# NucciF.net
KiCad netlist of a schematic drawn in Altium Designer
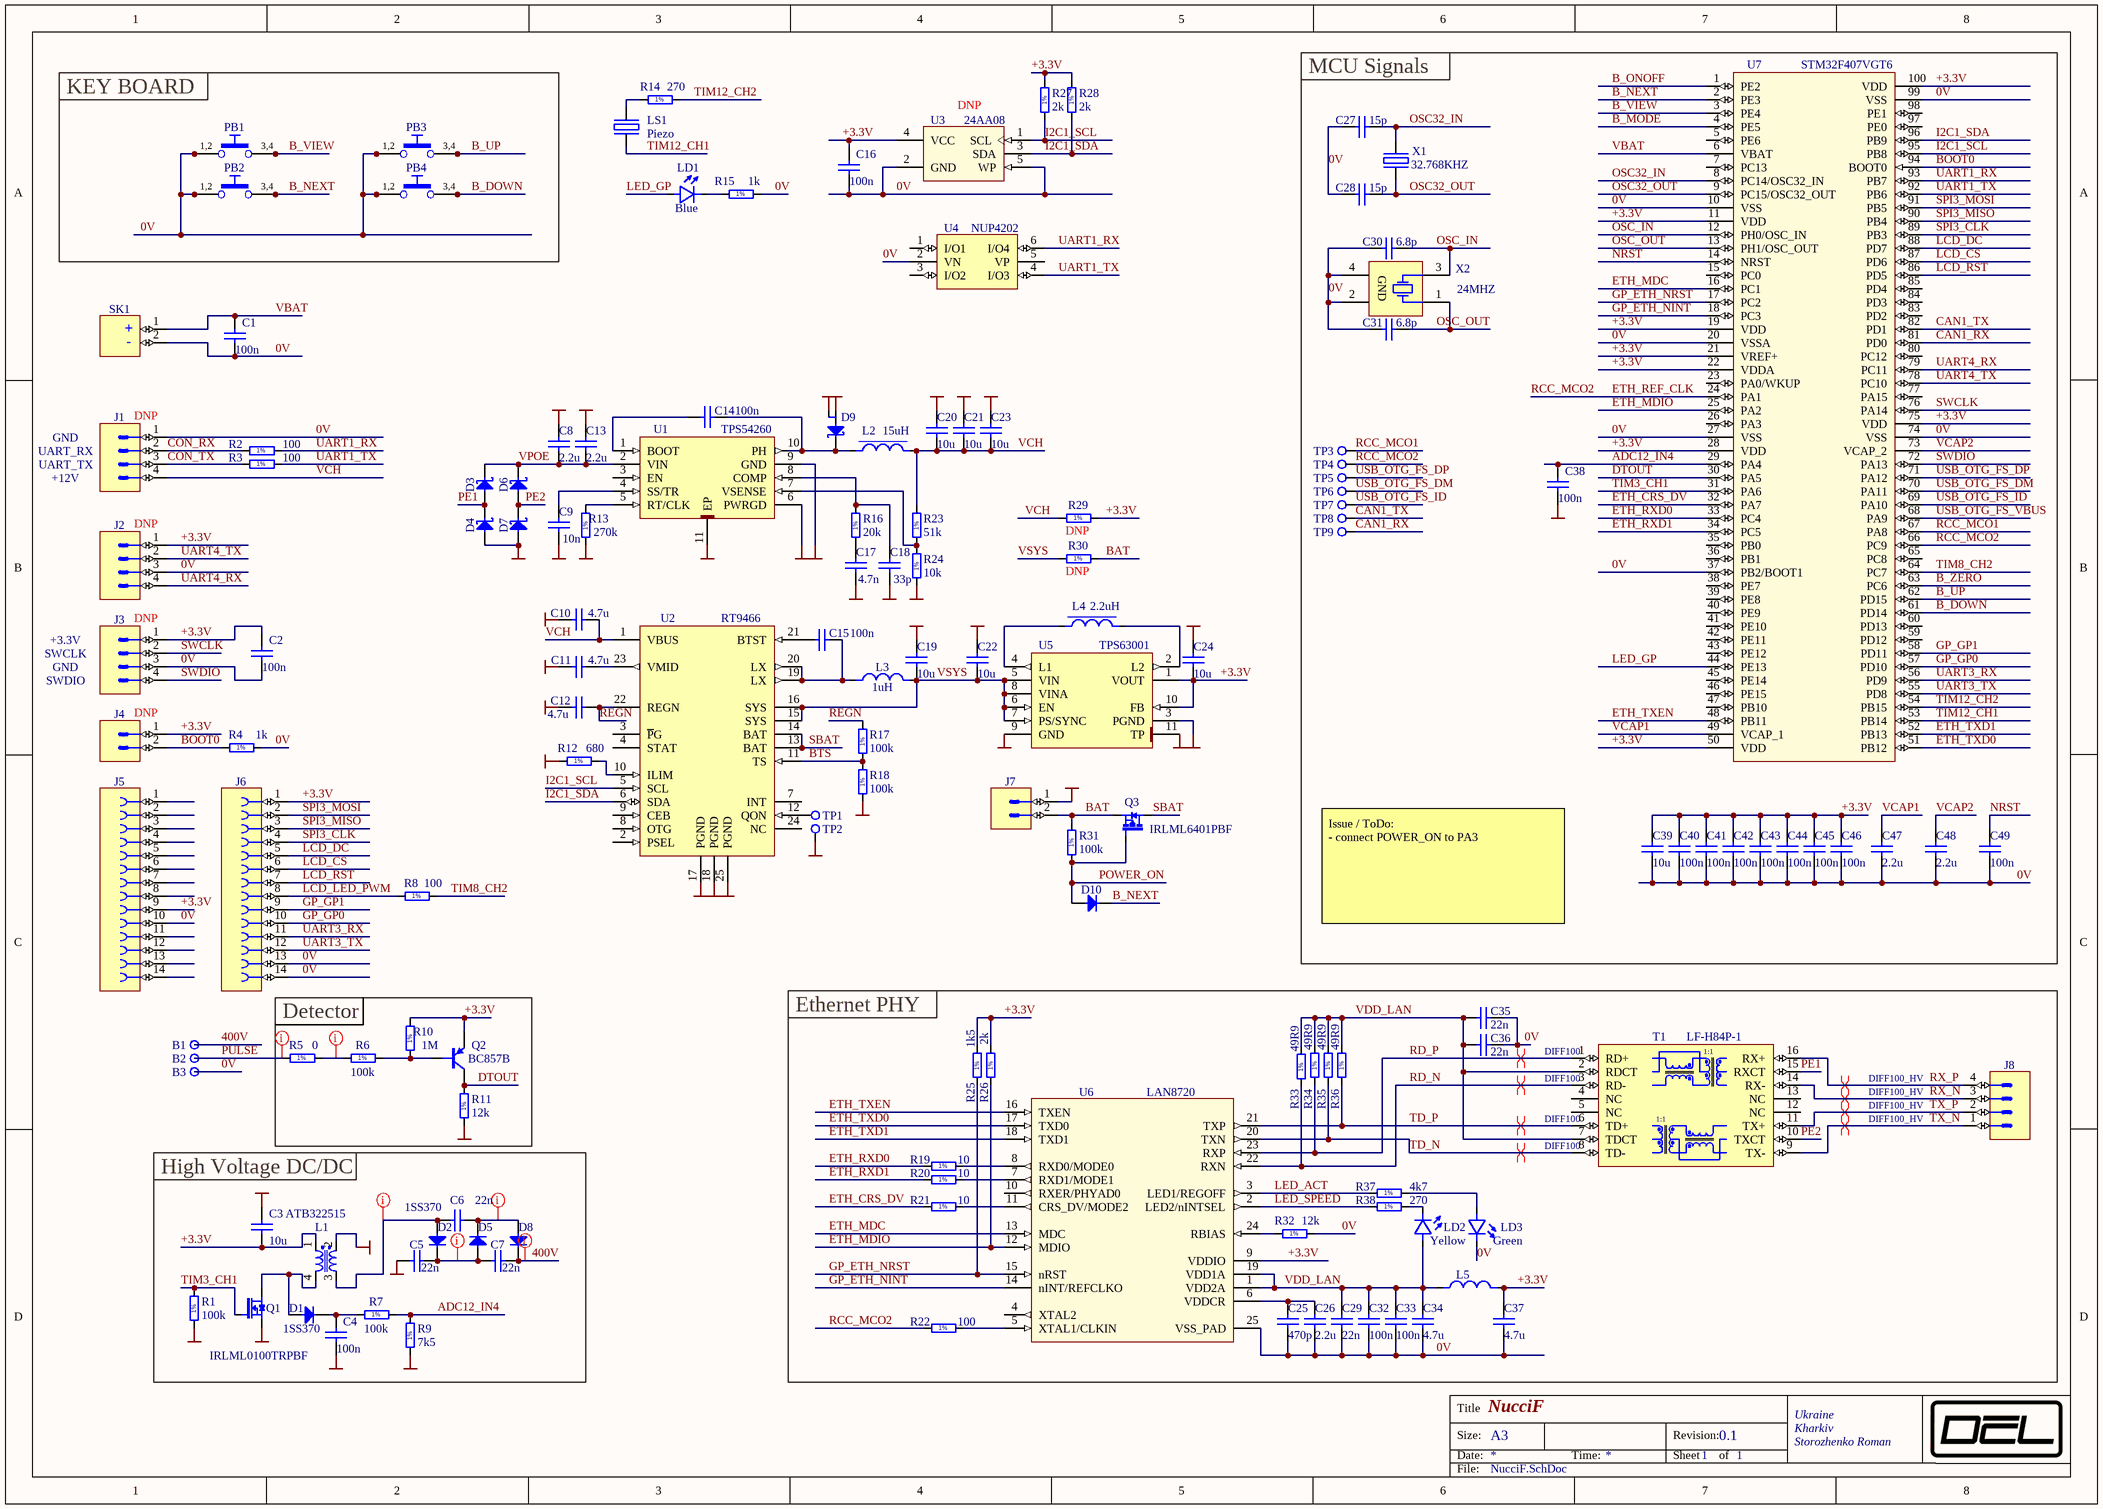
[diagram p0: NucciF.SchDoc]

(export (version "E")
  (design (tool "Eeschema 10.0.6"))
  (components
    (comp (ref "B1")
      (value "V")
      (footprint "c150h100")
      (description "Single Terminal Socket")
      (fields (field (name "PART NUMBER") "PLATED_HOLE1.0_PAD1.5") (field (name "AUTHOR") "CERN DEM JLC"))
      (libsource (lib "Eletro-mechanical") (part "Single Terminal Socket"))
    )
    (comp (ref "B2")
      (value "P")
      (footprint "c150h100")
      (description "Single Terminal Socket")
      (fields (field (name "PART NUMBER") "PLATED_HOLE1.0_PAD1.5") (field (name "AUTHOR") "CERN DEM JLC"))
      (libsource (lib "Eletro-mechanical") (part "Single Terminal Socket"))
    )
    (comp (ref "B3")
      (value "G")
      (footprint "c150h100")
      (description "Single Terminal Socket")
      (fields (field (name "PART NUMBER") "PLATED_HOLE1.0_PAD1.5") (field (name "AUTHOR") "CERN DEM JLC"))
      (libsource (lib "Eletro-mechanical") (part "Single Terminal Socket"))
    )
    (comp (ref "C1")
      (value "100n")
      (footprint "CAPC1005X55N")
      (description "Non-polarised capacitor")
      (fields
        (field (name "PART NUMBER") "CC0402_100NF_50V_10%_X7R")
        (field (name "VOLTAGE") "50V")
        (field (name "AUTHOR") "DEL")
      )
      (libsource (lib "Capacitors") (part "Capacitor - non polarized"))
    )
    (comp (ref "C2")
      (value "100n")
      (footprint "CAPC1005X55N")
      (description "Non-polarised capacitor")
      (fields
        (field (name "PART NUMBER") "CC0402_100NF_50V_10%_X7R")
        (field (name "VOLTAGE") "50V")
        (field (name "AUTHOR") "DEL")
      )
      (libsource (lib "Capacitors") (part "Capacitor - non polarized"))
    )
    (comp (ref "C3")
      (value "10u")
      (footprint "CAPC1608X87N")
      (description "Non-polarised capacitor")
      (fields
        (field (name "PART NUMBER") "CC0603_10UF_10V_20%_X5R")
        (field (name "VOLTAGE") "10V")
        (field (name "AUTHOR") "CERN DEM JLC")
      )
      (libsource (lib "Capacitors") (part "Capacitor - non polarized"))
    )
    (comp (ref "C4")
      (value "100n")
      (footprint "CAPC1005X55N")
      (description "Non-polarised capacitor")
      (fields
        (field (name "PART NUMBER") "CC0402_100NF_50V_10%_X7R")
        (field (name "VOLTAGE") "50V")
        (field (name "AUTHOR") "DEL")
      )
      (libsource (lib "Capacitors") (part "Capacitor - non polarized"))
    )
    (comp (ref "C5")
      (value "22n")
      (footprint "CAPC2012X135N")
      (description "Non-polarised capacitor")
      (fields
        (field (name "PART NUMBER") "CC0805_22NF_500V_10%_X7R")
        (field (name "VOLTAGE") "500V")
        (field (name "AUTHOR") "DEL")
      )
      (libsource (lib "Capacitors") (part "Capacitor - non polarized"))
    )
    (comp (ref "C6")
      (value "22n")
      (footprint "CAPC2012X135N")
      (description "Non-polarised capacitor")
      (fields
        (field (name "PART NUMBER") "CC0805_22NF_500V_10%_X7R")
        (field (name "VOLTAGE") "500V")
        (field (name "AUTHOR") "DEL")
      )
      (libsource (lib "Capacitors") (part "Capacitor - non polarized"))
    )
    (comp (ref "C7")
      (value "22n")
      (footprint "CAPC2012X135N")
      (description "Non-polarised capacitor")
      (fields
        (field (name "PART NUMBER") "CC0805_22NF_500V_10%_X7R")
        (field (name "VOLTAGE") "500V")
        (field (name "AUTHOR") "DEL")
      )
      (libsource (lib "Capacitors") (part "Capacitor - non polarized"))
    )
    (comp (ref "C8")
      (value "2.2u")
      (footprint "CAPC3216X140N")
      (description "Non-polarised capacitor")
      (fields
        (field (name "PART NUMBER") "CC1206_2.2UF_100V_10%_X7R")
        (field (name "VOLTAGE") "100V")
        (field (name "AUTHOR") "DEL")
      )
      (libsource (lib "Capacitors") (part "Capacitor - non polarized"))
    )
    (comp (ref "C9")
      (value "10n")
      (footprint "CAPC1005X55N")
      (description "Non-polarised capacitor")
      (fields
        (field (name "PART NUMBER") "CC0402_10NF_16V_10%_X7R")
        (field (name "VOLTAGE") "16V")
        (field (name "AUTHOR") "CERN DEM JLC")
      )
      (libsource (lib "Capacitors") (part "Capacitor - non polarized"))
    )
    (comp (ref "C10")
      (value "4.7u")
      (footprint "CAPC1005X55N")
      (description "Non-polarised capacitor")
      (fields
        (field (name "PART NUMBER") "CC0402_4.7UF_10V_20%_X5R")
        (field (name "VOLTAGE") "10V")
        (field (name "AUTHOR") "DEL")
      )
      (libsource (lib "Capacitors") (part "Capacitor - non polarized"))
    )
    (comp (ref "C11")
      (value "4.7u")
      (footprint "CAPC1005X55N")
      (description "Non-polarised capacitor")
      (fields
        (field (name "PART NUMBER") "CC0402_4.7UF_10V_20%_X5R")
        (field (name "VOLTAGE") "10V")
        (field (name "AUTHOR") "DEL")
      )
      (libsource (lib "Capacitors") (part "Capacitor - non polarized"))
    )
    (comp (ref "C12")
      (value "4.7u")
      (footprint "CAPC1005X55N")
      (description "Non-polarised capacitor")
      (fields
        (field (name "PART NUMBER") "CC0402_4.7UF_10V_20%_X5R")
        (field (name "VOLTAGE") "10V")
        (field (name "AUTHOR") "DEL")
      )
      (libsource (lib "Capacitors") (part "Capacitor - non polarized"))
    )
    (comp (ref "C13")
      (value "2.2u")
      (footprint "CAPC3216X140N")
      (description "Non-polarised capacitor")
      (fields
        (field (name "PART NUMBER") "CC1206_2.2UF_100V_10%_X7R")
        (field (name "VOLTAGE") "100V")
        (field (name "AUTHOR") "DEL")
      )
      (libsource (lib "Capacitors") (part "Capacitor - non polarized"))
    )
    (comp (ref "C14")
      (value "100n")
      (footprint "CAPC1005X55N")
      (description "Non-polarised capacitor")
      (fields
        (field (name "PART NUMBER") "CC0402_100NF_16V_10%_X7R")
        (field (name "VOLTAGE") "16V")
        (field (name "AUTHOR") "CERN DEM JLC")
      )
      (libsource (lib "Capacitors") (part "Capacitor - non polarized"))
    )
    (comp (ref "C15")
      (value "100n")
      (footprint "CAPC1005X55N")
      (description "Non-polarised capacitor")
      (fields
        (field (name "PART NUMBER") "CC0402_100NF_16V_10%_X7R")
        (field (name "VOLTAGE") "16V")
        (field (name "AUTHOR") "CERN DEM JLC")
      )
      (libsource (lib "Capacitors") (part "Capacitor - non polarized"))
    )
    (comp (ref "C16")
      (value "100n")
      (footprint "CAPC1005X55N")
      (description "Non-polarised capacitor")
      (fields
        (field (name "PART NUMBER") "CC0402_100NF_50V_10%_X7R")
        (field (name "VOLTAGE") "50V")
        (field (name "AUTHOR") "DEL")
      )
      (libsource (lib "Capacitors") (part "Capacitor - non polarized"))
    )
    (comp (ref "C17")
      (value "4.7n")
      (footprint "CAPC1005X55N")
      (description "Non-polarised capacitor")
      (fields
        (field (name "PART NUMBER") "CC0402_4.7NF_16V_10%_X7R")
        (field (name "VOLTAGE") "16V")
        (field (name "AUTHOR") "CERN DEM JLC")
      )
      (libsource (lib "Capacitors") (part "Capacitor - non polarized"))
    )
    (comp (ref "C18")
      (value "33p")
      (footprint "CAPC1005X55N")
      (description "Non-polarised capacitor")
      (fields
        (field (name "PART NUMBER") "CC0402_33PF_50V_5%_NP0")
        (field (name "VOLTAGE") "50V")
        (field (name "AUTHOR") "CERN DEM JLC")
      )
      (libsource (lib "Capacitors") (part "Capacitor - non polarized"))
    )
    (comp (ref "C19")
      (value "10u")
      (footprint "CAPC1608X87N")
      (description "Non-polarised capacitor")
      (fields
        (field (name "PART NUMBER") "CC0603_10UF_10V_20%_X5R")
        (field (name "VOLTAGE") "10V")
        (field (name "AUTHOR") "CERN DEM JLC")
      )
      (libsource (lib "Capacitors") (part "Capacitor - non polarized"))
    )
    (comp (ref "C20")
      (value "10u")
      (footprint "CAPC1608X87N")
      (description "Non-polarised capacitor")
      (fields
        (field (name "PART NUMBER") "CC0603_10UF_10V_20%_X5R")
        (field (name "VOLTAGE") "10V")
        (field (name "AUTHOR") "CERN DEM JLC")
      )
      (libsource (lib "Capacitors") (part "Capacitor - non polarized"))
    )
    (comp (ref "C21")
      (value "10u")
      (footprint "CAPC1608X87N")
      (description "Non-polarised capacitor")
      (fields
        (field (name "PART NUMBER") "CC0603_10UF_10V_20%_X5R")
        (field (name "VOLTAGE") "10V")
        (field (name "AUTHOR") "CERN DEM JLC")
      )
      (libsource (lib "Capacitors") (part "Capacitor - non polarized"))
    )
    (comp (ref "C22")
      (value "10u")
      (footprint "CAPC1608X87N")
      (description "Non-polarised capacitor")
      (fields
        (field (name "PART NUMBER") "CC0603_10UF_10V_20%_X5R")
        (field (name "VOLTAGE") "10V")
        (field (name "AUTHOR") "CERN DEM JLC")
      )
      (libsource (lib "Capacitors") (part "Capacitor - non polarized"))
    )
    (comp (ref "C23")
      (value "10u")
      (footprint "CAPC1608X87N")
      (description "Non-polarised capacitor")
      (fields
        (field (name "PART NUMBER") "CC0603_10UF_10V_20%_X5R")
        (field (name "VOLTAGE") "10V")
        (field (name "AUTHOR") "CERN DEM JLC")
      )
      (libsource (lib "Capacitors") (part "Capacitor - non polarized"))
    )
    (comp (ref "C24")
      (value "10u")
      (footprint "CAPC1608X87N")
      (description "Non-polarised capacitor")
      (fields
        (field (name "PART NUMBER") "CC0603_10UF_10V_20%_X5R")
        (field (name "VOLTAGE") "10V")
        (field (name "AUTHOR") "CERN DEM JLC")
      )
      (libsource (lib "Capacitors") (part "Capacitor - non polarized"))
    )
    (comp (ref "C25")
      (value "470p")
      (footprint "CAPC1005X55N")
      (description "Non-polarised capacitor")
      (fields
        (field (name "PART NUMBER") "CC0402_470PF_50V_10%_X7R")
        (field (name "VOLTAGE") "50V")
        (field (name "AUTHOR") "CERN DEM JLC")
      )
      (libsource (lib "Capacitors") (part "Capacitor - non polarized"))
    )
    (comp (ref "C26")
      (value "2.2u")
      (footprint "CAPC1005X55N")
      (description "Non-polarised capacitor")
      (fields
        (field (name "PART NUMBER") "CC0402_2.2UF_6.3V_20%_X5R")
        (field (name "VOLTAGE") "6.3V")
        (field (name "AUTHOR") "ELMAN")
      )
      (libsource (lib "Capacitors") (part "Capacitor - non polarized"))
    )
    (comp (ref "C27")
      (value "15p")
      (footprint "CAPC1005X55N")
      (description "Non-polarised capacitor")
      (fields
        (field (name "PART NUMBER") "CC0402_15PF_50V_5%_NP0")
        (field (name "VOLTAGE") "50V")
        (field (name "AUTHOR") "CERN DEM JLC")
      )
      (libsource (lib "Capacitors") (part "Capacitor - non polarized"))
    )
    (comp (ref "C28")
      (value "15p")
      (footprint "CAPC1005X55N")
      (description "Non-polarised capacitor")
      (fields
        (field (name "PART NUMBER") "CC0402_15PF_50V_5%_NP0")
        (field (name "VOLTAGE") "50V")
        (field (name "AUTHOR") "CERN DEM JLC")
      )
      (libsource (lib "Capacitors") (part "Capacitor - non polarized"))
    )
    (comp (ref "C29")
      (value "22n")
      (footprint "CAPC1005X55N")
      (description "Non-polarised capacitor")
      (fields
        (field (name "PART NUMBER") "CC0402_22NF_16V_10%_X7R")
        (field (name "VOLTAGE") "16V")
        (field (name "AUTHOR") "CERN DEM JLC")
      )
      (libsource (lib "Capacitors") (part "Capacitor - non polarized"))
    )
    (comp (ref "C30")
      (value "6.8p")
      (footprint "CAPC1005X55N")
      (description "Non-polarised capacitor")
      (fields
        (field (name "PART NUMBER") "CC0402_6.8PF_50V_0.5PF_NP0")
        (field (name "VOLTAGE") "50V")
        (field (name "AUTHOR") "CERN DEM JLC")
      )
      (libsource (lib "Capacitors") (part "Capacitor - non polarized"))
    )
    (comp (ref "C31")
      (value "6.8p")
      (footprint "CAPC1005X55N")
      (description "Non-polarised capacitor")
      (fields
        (field (name "PART NUMBER") "CC0402_6.8PF_50V_0.5PF_NP0")
        (field (name "VOLTAGE") "50V")
        (field (name "AUTHOR") "CERN DEM JLC")
      )
      (libsource (lib "Capacitors") (part "Capacitor - non polarized"))
    )
    (comp (ref "C32")
      (value "100n")
      (footprint "CAPC1005X55N")
      (description "Non-polarised capacitor")
      (fields
        (field (name "PART NUMBER") "CC0402_100NF_50V_10%_X7R")
        (field (name "VOLTAGE") "50V")
        (field (name "AUTHOR") "DEL")
      )
      (libsource (lib "Capacitors") (part "Capacitor - non polarized"))
    )
    (comp (ref "C33")
      (value "100n")
      (footprint "CAPC1005X55N")
      (description "Non-polarised capacitor")
      (fields
        (field (name "PART NUMBER") "CC0402_100NF_50V_10%_X7R")
        (field (name "VOLTAGE") "50V")
        (field (name "AUTHOR") "DEL")
      )
      (libsource (lib "Capacitors") (part "Capacitor - non polarized"))
    )
    (comp (ref "C34")
      (value "4.7u")
      (footprint "CAPC1608X87N")
      (description "Non-polarised capacitor")
      (fields
        (field (name "PART NUMBER") "CC0603_4.7UF_10V_10%_X5R")
        (field (name "VOLTAGE") "10V")
        (field (name "AUTHOR") "ELMAN")
      )
      (libsource (lib "Capacitors") (part "Capacitor - non polarized"))
    )
    (comp (ref "C35")
      (value "22n")
      (footprint "CAPC1005X55N")
      (description "Non-polarised capacitor")
      (fields
        (field (name "PART NUMBER") "CC0402_22NF_16V_10%_X7R")
        (field (name "VOLTAGE") "16V")
        (field (name "AUTHOR") "CERN DEM JLC")
      )
      (libsource (lib "Capacitors") (part "Capacitor - non polarized"))
    )
    (comp (ref "C36")
      (value "22n")
      (footprint "CAPC1005X55N")
      (description "Non-polarised capacitor")
      (fields
        (field (name "PART NUMBER") "CC0402_22NF_16V_10%_X7R")
        (field (name "VOLTAGE") "16V")
        (field (name "AUTHOR") "CERN DEM JLC")
      )
      (libsource (lib "Capacitors") (part "Capacitor - non polarized"))
    )
    (comp (ref "C37")
      (value "4.7u")
      (footprint "CAPC1608X87N")
      (description "Non-polarised capacitor")
      (fields
        (field (name "PART NUMBER") "CC0603_4.7UF_10V_10%_X5R")
        (field (name "VOLTAGE") "10V")
        (field (name "AUTHOR") "ELMAN")
      )
      (libsource (lib "Capacitors") (part "Capacitor - non polarized"))
    )
    (comp (ref "C38")
      (value "100n")
      (footprint "CAPC1005X55N")
      (description "Non-polarised capacitor")
      (fields
        (field (name "PART NUMBER") "CC0402_100NF_50V_10%_X7R")
        (field (name "VOLTAGE") "50V")
        (field (name "AUTHOR") "DEL")
      )
      (libsource (lib "Capacitors") (part "Capacitor - non polarized"))
    )
    (comp (ref "C39")
      (value "10u")
      (footprint "CAPC1608X87N")
      (description "Non-polarised capacitor")
      (fields
        (field (name "PART NUMBER") "CC0603_10UF_10V_20%_X5R")
        (field (name "VOLTAGE") "10V")
        (field (name "AUTHOR") "CERN DEM JLC")
      )
      (libsource (lib "Capacitors") (part "Capacitor - non polarized"))
    )
    (comp (ref "C40")
      (value "100n")
      (footprint "CAPC1005X55N")
      (description "Non-polarised capacitor")
      (fields
        (field (name "PART NUMBER") "CC0402_100NF_50V_10%_X7R")
        (field (name "VOLTAGE") "50V")
        (field (name "AUTHOR") "DEL")
      )
      (libsource (lib "Capacitors") (part "Capacitor - non polarized"))
    )
    (comp (ref "C41")
      (value "100n")
      (footprint "CAPC1005X55N")
      (description "Non-polarised capacitor")
      (fields
        (field (name "PART NUMBER") "CC0402_100NF_50V_10%_X7R")
        (field (name "VOLTAGE") "50V")
        (field (name "AUTHOR") "DEL")
      )
      (libsource (lib "Capacitors") (part "Capacitor - non polarized"))
    )
    (comp (ref "C42")
      (value "100n")
      (footprint "CAPC1005X55N")
      (description "Non-polarised capacitor")
      (fields
        (field (name "PART NUMBER") "CC0402_100NF_50V_10%_X7R")
        (field (name "VOLTAGE") "50V")
        (field (name "AUTHOR") "DEL")
      )
      (libsource (lib "Capacitors") (part "Capacitor - non polarized"))
    )
    (comp (ref "C43")
      (value "100n")
      (footprint "CAPC1005X55N")
      (description "Non-polarised capacitor")
      (fields
        (field (name "PART NUMBER") "CC0402_100NF_50V_10%_X7R")
        (field (name "VOLTAGE") "50V")
        (field (name "AUTHOR") "DEL")
      )
      (libsource (lib "Capacitors") (part "Capacitor - non polarized"))
    )
    (comp (ref "C44")
      (value "100n")
      (footprint "CAPC1005X55N")
      (description "Non-polarised capacitor")
      (fields
        (field (name "PART NUMBER") "CC0402_100NF_50V_10%_X7R")
        (field (name "VOLTAGE") "50V")
        (field (name "AUTHOR") "DEL")
      )
      (libsource (lib "Capacitors") (part "Capacitor - non polarized"))
    )
    (comp (ref "C45")
      (value "100n")
      (footprint "CAPC1005X55N")
      (description "Non-polarised capacitor")
      (fields
        (field (name "PART NUMBER") "CC0402_100NF_50V_10%_X7R")
        (field (name "VOLTAGE") "50V")
        (field (name "AUTHOR") "DEL")
      )
      (libsource (lib "Capacitors") (part "Capacitor - non polarized"))
    )
    (comp (ref "C46")
      (value "100n")
      (footprint "CAPC1005X55N")
      (description "Non-polarised capacitor")
      (fields
        (field (name "PART NUMBER") "CC0402_100NF_50V_10%_X7R")
        (field (name "VOLTAGE") "50V")
        (field (name "AUTHOR") "DEL")
      )
      (libsource (lib "Capacitors") (part "Capacitor - non polarized"))
    )
    (comp (ref "C47")
      (value "2.2u")
      (footprint "CAPC1005X55N")
      (description "Non-polarised capacitor")
      (fields
        (field (name "PART NUMBER") "CC0402_2.2UF_6.3V_20%_X5R")
        (field (name "VOLTAGE") "6.3V")
        (field (name "AUTHOR") "ELMAN")
      )
      (libsource (lib "Capacitors") (part "Capacitor - non polarized"))
    )
    (comp (ref "C48")
      (value "2.2u")
      (footprint "CAPC1005X55N")
      (description "Non-polarised capacitor")
      (fields
        (field (name "PART NUMBER") "CC0402_2.2UF_6.3V_20%_X5R")
        (field (name "VOLTAGE") "6.3V")
        (field (name "AUTHOR") "ELMAN")
      )
      (libsource (lib "Capacitors") (part "Capacitor - non polarized"))
    )
    (comp (ref "C49")
      (value "100n")
      (footprint "CAPC1005X55N")
      (description "Non-polarised capacitor")
      (fields
        (field (name "PART NUMBER") "CC0402_100NF_50V_10%_X7R")
        (field (name "VOLTAGE") "50V")
        (field (name "AUTHOR") "DEL")
      )
      (libsource (lib "Capacitors") (part "Capacitor - non polarized"))
    )
    (comp (ref "D1")
      (value "1SS370")
      (footprint "SOT65P210X100-3N")
      (description "Diode Anode Pin 1 Cathode Pin 3 (Pas de pin 2)")
      (fields (field (name "VOLTAGE") "40V") (field (name "POWER") "250mW") (field (name "AUTHOR") "DEL"))
      (libsource (lib "ICs And Semiconductors") (part "Diode A1C3"))
    )
    (comp (ref "D2")
      (value "1SS370")
      (footprint "SOT65P210X100-3N")
      (description "Diode Anode Pin 1 Cathode Pin 3 (Pas de pin 2)")
      (fields (field (name "VOLTAGE") "40V") (field (name "POWER") "250mW") (field (name "AUTHOR") "DEL"))
      (libsource (lib "ICs And Semiconductors") (part "Diode A1C3"))
    )
    (comp (ref "D3")
      (value "MBR0540T1G")
      (footprint "SOD3716X135N")
      (description "Schottky Diode")
      (fields
        (field (name "VOLTAGE") "40V")
        (field (name "POWER") "500mA")
        (field (name "AUTHOR") "CERN DEM JLC")
      )
      (libsource (lib "ICs And Semiconductors") (part "Diode Schottky"))
    )
    (comp (ref "D4")
      (value "MBR0540T1G")
      (footprint "SOD3716X135N")
      (description "Schottky Diode")
      (fields
        (field (name "VOLTAGE") "40V")
        (field (name "POWER") "500mA")
        (field (name "AUTHOR") "CERN DEM JLC")
      )
      (libsource (lib "ICs And Semiconductors") (part "Diode Schottky"))
    )
    (comp (ref "D5")
      (value "1SS370")
      (footprint "SOT65P210X100-3N")
      (description "Diode Anode Pin 1 Cathode Pin 3 (Pas de pin 2)")
      (fields (field (name "VOLTAGE") "40V") (field (name "POWER") "250mW") (field (name "AUTHOR") "DEL"))
      (libsource (lib "ICs And Semiconductors") (part "Diode A1C3"))
    )
    (comp (ref "D6")
      (value "MBR0540T1G")
      (footprint "SOD3716X135N")
      (description "Schottky Diode")
      (fields
        (field (name "VOLTAGE") "40V")
        (field (name "POWER") "500mA")
        (field (name "AUTHOR") "CERN DEM JLC")
      )
      (libsource (lib "ICs And Semiconductors") (part "Diode Schottky"))
    )
    (comp (ref "D7")
      (value "MBR0540T1G")
      (footprint "SOD3716X135N")
      (description "Schottky Diode")
      (fields
        (field (name "VOLTAGE") "40V")
        (field (name "POWER") "500mA")
        (field (name "AUTHOR") "CERN DEM JLC")
      )
      (libsource (lib "ICs And Semiconductors") (part "Diode Schottky"))
    )
    (comp (ref "D8")
      (value "1SS370")
      (footprint "SOT65P210X100-3N")
      (description "Diode Anode Pin 1 Cathode Pin 3 (Pas de pin 2)")
      (fields (field (name "VOLTAGE") "40V") (field (name "POWER") "250mW") (field (name "AUTHOR") "DEL"))
      (libsource (lib "ICs And Semiconductors") (part "Diode A1C3"))
    )
    (comp (ref "D9")
      (value "SBRT15U100SP5")
      (footprint "SBRT15U100SP5")
      (description "Diode  Schottky Anode pin 1 and 2 cathode pin 3")
      (fields (field (name "VOLTAGE") "100V") (field (name "POWER") "15A") (field (name "AUTHOR") "DEL"))
      (libsource (lib "ICs And Semiconductors") (part "Diode Schottky A1A2_C3"))
    )
    (comp (ref "D10")
      (value "1N4148W")
      (footprint "SOD3715X145N")
      (description "Diode")
      (fields (field (name "VOLTAGE") "75V") (field (name "POWER") "150mA") (field (name "AUTHOR") "DEL"))
      (libsource (lib "ICs And Semiconductors") (part "Diode"))
    )
    (comp (ref "J1")
      (value "Header 4")
      (footprint "3M_2304-6111-TG")
      (description "Connector 4 Male")
      (fields
        (field (name "PART NUMBER") "3M_2304-6111-TG")
        (field (name "MOUNTED") "DNP")
        (field (name "MANUFACTURER") "3M")
        (field (name "AUTHOR") "DEL")
      )
      (libsource (lib "Connectors") (part "Connector 4 Male"))
    )
    (comp (ref "J2")
      (value "Header 4")
      (footprint "3M_2304-6111-TG")
      (description "Connector 4 Male")
      (fields
        (field (name "PART NUMBER") "3M_2304-6111-TG")
        (field (name "MOUNTED") "DNP")
        (field (name "MANUFACTURER") "3M")
        (field (name "AUTHOR") "DEL")
      )
      (libsource (lib "Connectors") (part "Connector 4 Male"))
    )
    (comp (ref "J3")
      (value "Header 4")
      (footprint "3M_2304-6111-TG")
      (description "Connector 4 Male")
      (fields
        (field (name "PART NUMBER") "3M_2304-6111-TG")
        (field (name "MOUNTED") "DNP")
        (field (name "MANUFACTURER") "3M")
        (field (name "AUTHOR") "DEL")
      )
      (libsource (lib "Connectors") (part "Connector 4 Male"))
    )
    (comp (ref "J4")
      (value "Header 2")
      (footprint "3M_2302-6111-TG")
      (description "Connector 2 Male")
      (fields
        (field (name "PART NUMBER") "3M_2302-6111-TG")
        (field (name "MOUNTED") "DNP")
        (field (name "MANUFACTURER") "3M")
        (field (name "AUTHOR") "DEL")
      )
      (libsource (lib "Connectors") (part "Connector 2 Male"))
    )
    (comp (ref "J5")
      (value "Socket 14")
      (footprint "3M_955114-6102-AR")
      (description "Connector 14 Female")
      (fields
        (field (name "PART NUMBER") "3M_955114-6102-AR")
        (field (name "MANUFACTURER") "3M")
        (field (name "AUTHOR") "DEL")
      )
      (libsource (lib "Connectors") (part "Connector 14 Female"))
    )
    (comp (ref "J6")
      (value "Socket 14")
      (footprint "3M_955114-6102-AR")
      (description "Connector 14 Female")
      (fields
        (field (name "PART NUMBER") "3M_955114-6102-AR")
        (field (name "MANUFACTURER") "3M")
        (field (name "AUTHOR") "DEL")
      )
      (libsource (lib "Connectors") (part "Connector 14 Female"))
    )
    (comp (ref "J7")
      (value "Header 2")
      (footprint "3M_2302-6111-TG")
      (description "Connector 2 Male")
      (fields
        (field (name "PART NUMBER") "3M_2302-6111-TG")
        (field (name "MANUFACTURER") "3M")
        (field (name "AUTHOR") "DEL")
      )
      (libsource (lib "Connectors") (part "Connector 2 Male"))
    )
    (comp (ref "J8")
      (value "SPOX")
      (footprint "MOLEX_22-03-5045")
      (description "Connector 4 Male")
      (fields
        (field (name "PART NUMBER") "MOLEX_22-03-5045")
        (field (name "MANUFACTURER") "MOLEX")
        (field (name "AUTHOR") "DEL")
      )
      (libsource (lib "") (part "Connector 4 Male_1"))
    )
    (comp (ref "L1")
      (value "ATB322515")
      (footprint "XFMR_ATB322515-0110-T000")
      (description "Inductor Common Mode")
      (fields
        (field (name "PART NUMBER") "XFMR_TDK_ATB322515-0110-T000")
        (field (name "MANUFACTURER") "TDK")
        (field (name "AUTHOR") "DEL")
      )
      (libsource (lib "Inductors & Transformers") (part "Inductor Common Mode 1Dot-4 2Dot-3"))
    )
    (comp (ref "L2")
      (value "15uH")
      (footprint "IND_VISHAY_IHLP-2525CZ")
      (description "Inductor With Magnetic core")
      (fields
        (field (name "PART NUMBER") "IND_15UH_20%_HPI0630")
        (field (name "POWER") "2.7A")
        (field (name "AUTHOR") "DEL")
      )
      (libsource (lib "Inductors & Transformers") (part "Inductor With Magnetic core"))
    )
    (comp (ref "L3")
      (value "1uH")
      (footprint "IND_COILCRAFT_XAL4020")
      (description "Inductor")
      (fields
        (field (name "PART NUMBER") "IND_1UH_20%_COILCRAFT_XAL4020-102ME")
        (field (name "POWER") "9.6A")
        (field (name "AUTHOR") "ROMAN")
      )
      (libsource (lib "Inductors & Transformers") (part "Inductor"))
    )
    (comp (ref "L4")
      (value "2.2uH")
      (footprint "VLS3010CX-1")
      (description "Inductor With Magnetic core")
      (fields
        (field (name "PART NUMBER") "IND_2.2UH_20%_TDK_VLS3010CX-2R2M-1")
        (field (name "POWER") "1.11A")
        (field (name "AUTHOR") "DEL")
      )
      (libsource (lib "Inductors & Transformers") (part "Inductor With Magnetic core"))
    )
    (comp (ref "L5")
      (value "2.2uH")
      (footprint "INDC2520X100N")
      (description "Inductor")
      (fields
        (field (name "PART NUMBER") "IND1008_2.2UH_20%_TDK_MLP2520S2R2MT0S1")
        (field (name "POWER") "1.2A")
        (field (name "AUTHOR") "ELMAN")
      )
      (libsource (lib "Inductors & Transformers") (part "Inductor"))
    )
    (comp (ref "LD1")
      (value "Blue")
      (footprint "LEDC1608X80N_BLUE")
      (description "LED 1C 2A")
      (fields
        (field (name "PART NUMBER") "LED_OF-SMD1608B")
        (field (name "MANUFACTURER") "OPTOFLASH")
        (field (name "AUTHOR") "DEL")
      )
      (libsource (lib "ICs And Semiconductors") (part "LED 1C 2A"))
    )
    (comp (ref "LD2")
      (value "Yellow")
      (footprint "LEDC1608X80N_YELLOW")
      (description "LED 1C 2A")
      (fields
        (field (name "PART NUMBER") "LED_OF-SMD1608Y")
        (field (name "MANUFACTURER") "OPTOFLASH")
        (field (name "AUTHOR") "DEL")
      )
      (libsource (lib "ICs And Semiconductors") (part "LED 1C 2A"))
    )
    (comp (ref "LD3")
      (value "Green")
      (footprint "LEDC1608X80N_GREEN")
      (description "LED 1C 2A")
      (fields
        (field (name "PART NUMBER") "LED_OF-SMD1608G")
        (field (name "MANUFACTURER") "OPTOFLASH")
        (field (name "AUTHOR") "ELMAN")
      )
      (libsource (lib "ICs And Semiconductors") (part "LED 1C 2A"))
    )
    (comp (ref "LS1")
      (value "Piezo")
      (footprint "HPS13C")
      (description "Piezo Sounder")
      (fields
        (field (name "PART NUMBER") "HPS13C")
        (field (name "MANUFACTURER") "JL WORLD")
        (field (name "AUTHOR") "DEL")
      )
      (libsource (lib "Eletro-mechanical") (part "Piezo Sounder"))
    )
    (comp (ref "PB1")
      (value "Push Button")
      (footprint "PB_E-SWITCH_TL1105HF100Q")
      (description "Push-Button Switch SPDT")
      (fields
        (field (name "PART NUMBER") "PB_E-SWITCH_TL1105HF100Q")
        (field (name "MANUFACTURER") "E-SWITCH")
        (field (name "AUTHOR") "DEL")
      )
      (libsource (lib "Eletro-mechanical") (part "PB SPST 12NO-34NO"))
    )
    (comp (ref "PB2")
      (value "Push Button")
      (footprint "PB_E-SWITCH_TL1105HF100Q")
      (description "Push-Button Switch SPDT")
      (fields
        (field (name "PART NUMBER") "PB_E-SWITCH_TL1105HF100Q")
        (field (name "MANUFACTURER") "E-SWITCH")
        (field (name "AUTHOR") "DEL")
      )
      (libsource (lib "Eletro-mechanical") (part "PB SPST 12NO-34NO"))
    )
    (comp (ref "PB3")
      (value "Push Button")
      (footprint "PB_E-SWITCH_TL1105HF100Q")
      (description "Push-Button Switch SPDT")
      (fields
        (field (name "PART NUMBER") "PB_E-SWITCH_TL1105HF100Q")
        (field (name "MANUFACTURER") "E-SWITCH")
        (field (name "AUTHOR") "DEL")
      )
      (libsource (lib "Eletro-mechanical") (part "PB SPST 12NO-34NO"))
    )
    (comp (ref "PB4")
      (value "Push Button")
      (footprint "PB_E-SWITCH_TL1105HF100Q")
      (description "Push-Button Switch SPDT")
      (fields
        (field (name "PART NUMBER") "PB_E-SWITCH_TL1105HF100Q")
        (field (name "MANUFACTURER") "E-SWITCH")
        (field (name "AUTHOR") "DEL")
      )
      (libsource (lib "Eletro-mechanical") (part "PB SPST 12NO-34NO"))
    )
    (comp (ref "Q1")
      (value "IRLML0100TRPBF")
      (footprint "SOT95P237X112-3N")
      (description "N-CHANNEL MOSFET WITH DIODE")
      (fields (field (name "MANUFACTURER") "INTERNATIONAL RECTIFIER") (field (name "AUTHOR") "CERN DEM JLC"))
      (libsource (lib "ICs And Semiconductors") (part "N-MOSFET-D 1G 2S 3D"))
    )
    (comp (ref "Q2")
      (value "BC857B")
      (footprint "SOT95P230X110-3N")
      (description "PNP Transistor")
      (fields (field (name "MANUFACTURER") "NXP SEMICONDUCTORS") (field (name "AUTHOR") "CERN DEM JLC"))
      (libsource (lib "ICs And Semiconductors") (part "PNP B1 E2 C3"))
    )
    (comp (ref "Q3")
      (value "IRLML6401PBF")
      (footprint "SOT95P237X112-3N")
      (description "P-CHANNEL MOSFET WITH DIODE")
      (fields (field (name "MANUFACTURER") "INTERNATIONAL RECTIFIER") (field (name "AUTHOR") "CERN DEM JLC"))
      (libsource (lib "ICs And Semiconductors") (part "P-MOSFET-D 1G 2S 3D"))
    )
    (comp (ref "R1")
      (value "100k")
      (footprint "RESC1005X40N")
      (description "Resistor - 1%")
      (fields
        (field (name "PART NUMBER") "R0402_100K_1%_0.0625W_100PPM")
        (field (name "POWER") "0.0625W")
        (field (name "AUTHOR") "CERN DEM JLC")
      )
      (libsource (lib "Resistors") (part "Resistor - 1%"))
    )
    (comp (ref "R2")
      (value "100")
      (footprint "RESC1005X40N")
      (description "Resistor - 1%")
      (fields
        (field (name "PART NUMBER") "R0402_100R_1%_0.0625W_100PPM")
        (field (name "POWER") "0.0625W")
        (field (name "AUTHOR") "CERN DEM JLC")
      )
      (libsource (lib "Resistors") (part "Resistor - 1%"))
    )
    (comp (ref "R3")
      (value "100")
      (footprint "RESC1005X40N")
      (description "Resistor - 1%")
      (fields
        (field (name "PART NUMBER") "R0402_100R_1%_0.0625W_100PPM")
        (field (name "POWER") "0.0625W")
        (field (name "AUTHOR") "CERN DEM JLC")
      )
      (libsource (lib "Resistors") (part "Resistor - 1%"))
    )
    (comp (ref "R4")
      (value "1k")
      (footprint "RESC1005X40N")
      (description "Resistor - 1%")
      (fields
        (field (name "PART NUMBER") "R0402_1K_1%_0.0625W_100PPM")
        (field (name "POWER") "0.0625W")
        (field (name "AUTHOR") "CERN DEM JLC")
      )
      (libsource (lib "Resistors") (part "Resistor - 1%"))
    )
    (comp (ref "R5")
      (value "0")
      (footprint "RESC2012X60N")
      (description "Resistor - 1%")
      (fields
        (field (name "PART NUMBER") "R0805_0R_JUMPER")
        (field (name "MANUFACTURER") "GENERIC")
        (field (name "AUTHOR") "CERN DEM JLC")
      )
      (libsource (lib "Resistors") (part "Resistor - 1%"))
    )
    (comp (ref "R6")
      (value "100k")
      (footprint "RESC2012X60N")
      (description "Resistor - 1%")
      (fields
        (field (name "PART NUMBER") "R0805_100K_1%_0.125W_100PPM")
        (field (name "POWER") "0.125W")
        (field (name "AUTHOR") "CERN DEM JLC")
      )
      (libsource (lib "Resistors") (part "Resistor - 1%"))
    )
    (comp (ref "R7")
      (value "100k")
      (footprint "RESC1005X40N")
      (description "Resistor - 1%")
      (fields
        (field (name "PART NUMBER") "R0402_100K_1%_0.0625W_100PPM")
        (field (name "POWER") "0.0625W")
        (field (name "AUTHOR") "CERN DEM JLC")
      )
      (libsource (lib "Resistors") (part "Resistor - 1%"))
    )
    (comp (ref "R8")
      (value "100")
      (footprint "RESC1005X40N")
      (description "Resistor - 1%")
      (fields
        (field (name "PART NUMBER") "R0402_100R_1%_0.0625W_100PPM")
        (field (name "POWER") "0.0625W")
        (field (name "AUTHOR") "CERN DEM JLC")
      )
      (libsource (lib "Resistors") (part "Resistor - 1%"))
    )
    (comp (ref "R9")
      (value "7k5")
      (footprint "RESC1005X40N")
      (description "Resistor - 1%")
      (fields
        (field (name "PART NUMBER") "R0402_7K5_1%_0.0625W_100PPM")
        (field (name "POWER") "0.0625W")
        (field (name "AUTHOR") "CERN DEM JLC")
      )
      (libsource (lib "Resistors") (part "Resistor - 1%"))
    )
    (comp (ref "R10")
      (value "1M")
      (footprint "RESC1005X40N")
      (description "Resistor - 1%")
      (fields
        (field (name "PART NUMBER") "R0402_1M_1%_0.0625W_100PPM")
        (field (name "POWER") "0.0625W")
        (field (name "AUTHOR") "CERN DEM JLC")
      )
      (libsource (lib "Resistors") (part "Resistor - 1%"))
    )
    (comp (ref "R11")
      (value "12k")
      (footprint "RESC1005X40N")
      (description "Resistor - 1%")
      (fields
        (field (name "PART NUMBER") "R0402_12K_1%_0.0625W_100PPM")
        (field (name "POWER") "0.0625W")
        (field (name "AUTHOR") "CERN DEM JLC")
      )
      (libsource (lib "Resistors") (part "Resistor - 1%"))
    )
    (comp (ref "R12")
      (value "680")
      (footprint "RESC1005X40N")
      (description "Resistor - 1%")
      (fields
        (field (name "PART NUMBER") "R0402_680R_1%_0.0625W_100PPM")
        (field (name "POWER") "0.0625W")
        (field (name "AUTHOR") "CERN DEM JLC")
      )
      (libsource (lib "Resistors") (part "Resistor - 1%"))
    )
    (comp (ref "R13")
      (value "270k")
      (footprint "RESC1005X40N")
      (description "Resistor - 1%")
      (fields
        (field (name "PART NUMBER") "R0402_270K_1%_0.0625W_100PPM")
        (field (name "POWER") "0.0625W")
        (field (name "AUTHOR") "CERN DEM JLC")
      )
      (libsource (lib "Resistors") (part "Resistor - 1%"))
    )
    (comp (ref "R14")
      (value "270")
      (footprint "RESC1005X40N")
      (description "Resistor - 1%")
      (fields
        (field (name "PART NUMBER") "R0402_270R_1%_0.0625W_100PPM")
        (field (name "POWER") "0.0625W")
        (field (name "AUTHOR") "CERN DEM JLC")
      )
      (libsource (lib "Resistors") (part "Resistor - 1%"))
    )
    (comp (ref "R15")
      (value "1k")
      (footprint "RESC1005X40N")
      (description "Resistor - 1%")
      (fields
        (field (name "PART NUMBER") "R0402_1K_1%_0.0625W_100PPM")
        (field (name "POWER") "0.0625W")
        (field (name "AUTHOR") "CERN DEM JLC")
      )
      (libsource (lib "Resistors") (part "Resistor - 1%"))
    )
    (comp (ref "R16")
      (value "20k")
      (footprint "RESC1005X40N")
      (description "Resistor - 1%")
      (fields
        (field (name "PART NUMBER") "R0402_20K_1%_0.0625W_100PPM")
        (field (name "POWER") "0.0625W")
        (field (name "AUTHOR") "CERN DEM JLC")
      )
      (libsource (lib "Resistors") (part "Resistor - 1%"))
    )
    (comp (ref "R17")
      (value "100k")
      (footprint "RESC1005X40N")
      (description "Resistor - 1%")
      (fields
        (field (name "PART NUMBER") "R0402_100K_1%_0.0625W_100PPM")
        (field (name "POWER") "0.0625W")
        (field (name "AUTHOR") "CERN DEM JLC")
      )
      (libsource (lib "Resistors") (part "Resistor - 1%"))
    )
    (comp (ref "R18")
      (value "100k")
      (footprint "RESC1005X40N")
      (description "Resistor - 1%")
      (fields
        (field (name "PART NUMBER") "R0402_100K_1%_0.0625W_100PPM")
        (field (name "POWER") "0.0625W")
        (field (name "AUTHOR") "CERN DEM JLC")
      )
      (libsource (lib "Resistors") (part "Resistor - 1%"))
    )
    (comp (ref "R19")
      (value "10")
      (footprint "RESC1005X40N")
      (description "Resistor - 1%")
      (fields
        (field (name "PART NUMBER") "R0402_10R_1%_0.0625W_200PPM")
        (field (name "POWER") "0.0625W")
        (field (name "AUTHOR") "CERN DEM JLC")
      )
      (libsource (lib "Resistors") (part "Resistor - 1%"))
    )
    (comp (ref "R20")
      (value "10")
      (footprint "RESC1005X40N")
      (description "Resistor - 1%")
      (fields
        (field (name "PART NUMBER") "R0402_10R_1%_0.0625W_200PPM")
        (field (name "POWER") "0.0625W")
        (field (name "AUTHOR") "CERN DEM JLC")
      )
      (libsource (lib "Resistors") (part "Resistor - 1%"))
    )
    (comp (ref "R21")
      (value "10")
      (footprint "RESC1005X40N")
      (description "Resistor - 1%")
      (fields
        (field (name "PART NUMBER") "R0402_10R_1%_0.0625W_200PPM")
        (field (name "POWER") "0.0625W")
        (field (name "AUTHOR") "CERN DEM JLC")
      )
      (libsource (lib "Resistors") (part "Resistor - 1%"))
    )
    (comp (ref "R22")
      (value "100")
      (footprint "RESC1005X40N")
      (description "Resistor - 1%")
      (fields
        (field (name "PART NUMBER") "R0402_100R_1%_0.0625W_100PPM")
        (field (name "POWER") "0.0625W")
        (field (name "AUTHOR") "CERN DEM JLC")
      )
      (libsource (lib "Resistors") (part "Resistor - 1%"))
    )
    (comp (ref "R23")
      (value "51k")
      (footprint "RESC1005X40N")
      (description "Resistor - 1%")
      (fields
        (field (name "PART NUMBER") "R0402_51K_1%_0.0625W_100PPM")
        (field (name "POWER") "0.0625W")
        (field (name "AUTHOR") "CERN DEM JLC")
      )
      (libsource (lib "Resistors") (part "Resistor - 1%"))
    )
    (comp (ref "R24")
      (value "10k")
      (footprint "RESC1005X40N")
      (description "Resistor - 1%")
      (fields
        (field (name "PART NUMBER") "R0402_10K_1%_0.0625W_100PPM")
        (field (name "POWER") "0.0625W")
        (field (name "AUTHOR") "CERN DEM JLC")
      )
      (libsource (lib "Resistors") (part "Resistor - 1%"))
    )
    (comp (ref "R25")
      (value "1k5")
      (footprint "RESC1005X40N")
      (description "Resistor - 1%")
      (fields
        (field (name "PART NUMBER") "R0402_1K5_1%_0.0625W_100PPM")
        (field (name "POWER") "0.0625W")
        (field (name "AUTHOR") "CERN DEM JLC")
      )
      (libsource (lib "Resistors") (part "Resistor - 1%"))
    )
    (comp (ref "R26")
      (value "2k")
      (footprint "RESC1005X40N")
      (description "Resistor - 1%")
      (fields
        (field (name "PART NUMBER") "R0402_2K_1%_0.0625W_100PPM")
        (field (name "POWER") "0.0625W")
        (field (name "AUTHOR") "CERN DEM JLC")
      )
      (libsource (lib "Resistors") (part "Resistor - 1%"))
    )
    (comp (ref "R27")
      (value "2k")
      (footprint "RESC1005X40N")
      (description "Resistor - 1%")
      (fields
        (field (name "PART NUMBER") "R0402_2K_1%_0.0625W_100PPM")
        (field (name "POWER") "0.0625W")
        (field (name "AUTHOR") "CERN DEM JLC")
      )
      (libsource (lib "Resistors") (part "Resistor - 1%"))
    )
    (comp (ref "R28")
      (value "2k")
      (footprint "RESC1005X40N")
      (description "Resistor - 1%")
      (fields
        (field (name "PART NUMBER") "R0402_2K_1%_0.0625W_100PPM")
        (field (name "POWER") "0.0625W")
        (field (name "AUTHOR") "CERN DEM JLC")
      )
      (libsource (lib "Resistors") (part "Resistor - 1%"))
    )
    (comp (ref "R29")
      (value "0")
      (footprint "RESC1005X40N")
      (description "Resistor - 1%")
      (fields
        (field (name "PART NUMBER") "R0402_0R_JUMPER")
        (field (name "MANUFACTURER") "GENERIC")
        (field (name "MOUNTED") "DNP")
        (field (name "AUTHOR") "CERN DEM JLC")
      )
      (libsource (lib "Resistors") (part "Resistor - 1%"))
    )
    (comp (ref "R30")
      (value "0")
      (footprint "RESC1005X40N")
      (description "Resistor - 1%")
      (fields
        (field (name "PART NUMBER") "R0402_0R_JUMPER")
        (field (name "MANUFACTURER") "GENERIC")
        (field (name "MOUNTED") "DNP")
        (field (name "AUTHOR") "CERN DEM JLC")
      )
      (libsource (lib "Resistors") (part "Resistor - 1%"))
    )
    (comp (ref "R31")
      (value "100k")
      (footprint "RESC1005X40N")
      (description "Resistor - 1%")
      (fields
        (field (name "PART NUMBER") "R0402_100K_1%_0.0625W_100PPM")
        (field (name "POWER") "0.0625W")
        (field (name "AUTHOR") "CERN DEM JLC")
      )
      (libsource (lib "Resistors") (part "Resistor - 1%"))
    )
    (comp (ref "R32")
      (value "12k")
      (footprint "RESC1005X40N")
      (description "Resistor - 1%")
      (fields
        (field (name "PART NUMBER") "R0402_12K_1%_0.0625W_100PPM")
        (field (name "POWER") "0.0625W")
        (field (name "AUTHOR") "CERN DEM JLC")
      )
      (libsource (lib "Resistors") (part "Resistor - 1%"))
    )
    (comp (ref "R33")
      (value "49R9")
      (footprint "RESC1005X40N")
      (description "Resistor - 1%")
      (fields
        (field (name "PART NUMBER") "R0402_49R9_1%_0.0625W_100PPM")
        (field (name "POWER") "0.0625W")
        (field (name "AUTHOR") "ELMAN")
      )
      (libsource (lib "Resistors") (part "Resistor - 1%"))
    )
    (comp (ref "R34")
      (value "49R9")
      (footprint "RESC1005X40N")
      (description "Resistor - 1%")
      (fields
        (field (name "PART NUMBER") "R0402_49R9_1%_0.0625W_100PPM")
        (field (name "POWER") "0.0625W")
        (field (name "AUTHOR") "ELMAN")
      )
      (libsource (lib "Resistors") (part "Resistor - 1%"))
    )
    (comp (ref "R35")
      (value "49R9")
      (footprint "RESC1005X40N")
      (description "Resistor - 1%")
      (fields
        (field (name "PART NUMBER") "R0402_49R9_1%_0.0625W_100PPM")
        (field (name "POWER") "0.0625W")
        (field (name "AUTHOR") "ELMAN")
      )
      (libsource (lib "Resistors") (part "Resistor - 1%"))
    )
    (comp (ref "R36")
      (value "49R9")
      (footprint "RESC1005X40N")
      (description "Resistor - 1%")
      (fields
        (field (name "PART NUMBER") "R0402_49R9_1%_0.0625W_100PPM")
        (field (name "POWER") "0.0625W")
        (field (name "AUTHOR") "ELMAN")
      )
      (libsource (lib "Resistors") (part "Resistor - 1%"))
    )
    (comp (ref "R37")
      (value "4k7")
      (footprint "RESC1005X40N")
      (description "Resistor - 1%")
      (fields
        (field (name "PART NUMBER") "R0402_4K7_1%_0.0625W_100PPM")
        (field (name "POWER") "0.0625W")
        (field (name "AUTHOR") "CERN DEM JLC")
      )
      (libsource (lib "Resistors") (part "Resistor - 1%"))
    )
    (comp (ref "R38")
      (value "270")
      (footprint "RESC1005X40N")
      (description "Resistor - 1%")
      (fields
        (field (name "PART NUMBER") "R0402_270R_1%_0.0625W_100PPM")
        (field (name "POWER") "0.0625W")
        (field (name "AUTHOR") "CERN DEM JLC")
      )
      (libsource (lib "Resistors") (part "Resistor - 1%"))
    )
    (comp (ref "SK1")
      (value "BH500")
      (footprint "EEMB_BH500")
      (description "Battery holder")
      (fields
        (field (name "PART NUMBER") "EEMB_BH500")
        (field (name "MANUFACTURER") "EEMB")
        (field (name "AUTHOR") "DEL")
      )
      (libsource (lib "Eletro-mechanical") (part "BAT_HOLDER"))
    )
    (comp (ref "T1")
      (value "LF-H84P-1")
      (footprint "XFMR_LF-H84P")
      (description "Signal Transformers 10/100 Base-T XFMR 1 Port LAN")
      (fields
        (field (name "PART NUMBER") "PE-68678")
        (field (name "MANUFACTURER") "LANKom")
        (field (name "AUTHOR") "DEL")
      )
      (libsource (lib "Inductors & Transformers") (part "XFMR_10/100 Base-T"))
    )
    (comp (ref "TP1")
      (value "Test Point")
      (footprint "TP_SMD_800")
      (fields (field (name "PART NUMBER") "TP_SMD_0.8MM") (field (name "AUTHOR") "DEL"))
      (libsource (lib "Eletro-mechanical") (part "Test Point"))
    )
    (comp (ref "TP2")
      (value "GND")
      (footprint "TP_SMD_800")
      (fields (field (name "PART NUMBER") "TP_SMD_0.8MM") (field (name "AUTHOR") "DEL"))
      (libsource (lib "Eletro-mechanical") (part "Test Point"))
    )
    (comp (ref "TP3")
      (value "Test Point")
      (footprint "TP_SMD_800")
      (fields (field (name "PART NUMBER") "TP_SMD_0.8MM") (field (name "AUTHOR") "DEL"))
      (libsource (lib "Eletro-mechanical") (part "Test Point"))
    )
    (comp (ref "TP4")
      (value "Test Point")
      (footprint "TP_SMD_800")
      (fields (field (name "PART NUMBER") "TP_SMD_0.8MM") (field (name "AUTHOR") "DEL"))
      (libsource (lib "Eletro-mechanical") (part "Test Point"))
    )
    (comp (ref "TP5")
      (value "Test Point")
      (footprint "TP_SMD_800")
      (fields (field (name "PART NUMBER") "TP_SMD_0.8MM") (field (name "AUTHOR") "DEL"))
      (libsource (lib "Eletro-mechanical") (part "Test Point"))
    )
    (comp (ref "TP6")
      (value "Test Point")
      (footprint "TP_SMD_800")
      (fields (field (name "PART NUMBER") "TP_SMD_0.8MM") (field (name "AUTHOR") "DEL"))
      (libsource (lib "Eletro-mechanical") (part "Test Point"))
    )
    (comp (ref "TP7")
      (value "Test Point")
      (footprint "TP_SMD_800")
      (fields (field (name "PART NUMBER") "TP_SMD_0.8MM") (field (name "AUTHOR") "DEL"))
      (libsource (lib "Eletro-mechanical") (part "Test Point"))
    )
    (comp (ref "TP8")
      (value "Test Point")
      (footprint "TP_SMD_800")
      (fields (field (name "PART NUMBER") "TP_SMD_0.8MM") (field (name "AUTHOR") "DEL"))
      (libsource (lib "Eletro-mechanical") (part "Test Point"))
    )
    (comp (ref "TP9")
      (value "Test Point")
      (footprint "TP_SMD_800")
      (fields (field (name "PART NUMBER") "TP_SMD_0.8MM") (field (name "AUTHOR") "DEL"))
      (libsource (lib "Eletro-mechanical") (part "Test Point"))
    )
    (comp (ref "U1")
      (value "TPS54260")
      (footprint "SOP50P490X110-11N-R157X188")
      (fields
        (field (name "PART NUMBER") "TPS54260DGQ")
        (field (name "MANUFACTURER") "TEXAS INSTRUMENTS")
        (field (name "AUTHOR") "DEL")
      )
      (libsource (lib "ICs And Semiconductors") (part "TPS54260"))
    )
    (comp (ref "U2")
      (value "RT9466")
      (footprint "QFN50P400X400X100-25N-S270")
      (description "5A Single Cell Li-Ion Switching Battery Charger with Power Path Management and USB-OTG Boost Mode")
      (fields (field (name "MANUFACTURER") "Richtek") (field (name "AUTHOR") "DEL"))
      (libsource (lib "ICs And Semiconductors") (part "RT9466"))
    )
    (comp (ref "U3")
      (value "24AA08")
      (footprint "SOT95P280X145-5N")
      (description "I2C™ Serial EEPROM SOT23-5 Package")
      (fields
        (field (name "PART NUMBER") "24AA08T-I/OT")
        (field (name "MANUFACTURER") "MICROCHIP")
        (field (name "AUTHOR") "DEL")
      )
      (libsource (lib "ICs And Semiconductors") (part "24AAxxT-x/OT"))
    )
    (comp (ref "U4")
      (value "NUP4202")
      (footprint "SOT65P220X110-6N")
      (description "ESD Protection Diode, Low  Clamping Voltage")
      (fields
        (field (name "PART NUMBER") "NUP4202W1")
        (field (name "MANUFACTURER") "ON SEMICONDUCTOR")
        (field (name "MOUNTED") "DNP")
        (field (name "AUTHOR") "DEL")
      )
      (libsource (lib "ICs And Semiconductors") (part "NUP4202"))
    )
    (comp (ref "U5")
      (value "TPS63001")
      (footprint "SON50P300X300X100-11N-R175X250")
      (description "Single Inductor Buck-Boost Converter With 1.8-A Switches")
      (fields
        (field (name "MANUFACTURER") "TEXAS INSTRUMENTS")
        (field (name "MANUFACTURER PART NUMBER") "TPS63001DRCT")
        (field (name "AUTHOR") "DEL")
      )
      (libsource (lib "ICs And Semiconductors") (part "TPS6300x"))
    )
    (comp (ref "U6")
      (value "LAN8720")
      (footprint "QFN50P400X400X100-25N-S265")
      (fields
        (field (name "PART NUMBER") "LAN8720A-CP-TR")
        (field (name "MANUFACTURER") "Microchip")
        (field (name "AUTHOR") "DEL")
      )
      (libsource (lib "ICs And Semiconductors") (part "LAN8720"))
    )
    (comp (ref "U7")
      (value "STM32F407VGT6")
      (footprint "QFP50P1600X1600X160-100N")
      (fields (field (name "MANUFACTURER") "ST Microelectronics") (field (name "AUTHOR") "DEL"))
      (libsource (lib "ICs And Semiconductors") (part "STM32F407VxT"))
    )
    (comp (ref "X1")
      (value "32.768KHZ")
      (footprint "OSCCC150X320X80-2N")
      (description "Quartz Crystal")
      (fields
        (field (name "PART NUMBER") "32.768KHz_KX–327NHT")
        (field (name "MANUFACTURER") "GEYER")
        (field (name "AUTHOR") "D_EL")
      )
      (libsource (lib "Crystals & Oscillators") (part "Quartz Crystal"))
    )
    (comp (ref "X2")
      (value "24MHZ")
      (footprint "OSCCC160X200X65-4N")
      (description "Crystal 4 pins 1=XTAL 2=GND3=XTAL 4=GND")
      (fields
        (field (name "PART NUMBER") "24MHZ_XRCGB24M000F3M00R0")
        (field (name "MANUFACTURER") "MURATA")
        (field (name "AUTHOR") "D_EL")
      )
      (libsource (lib "Crystals & Oscillators") (part "Quartz Crystal 1X 2GND 3X 4GND"))
    )
  )
  (nets
    (net (code "1") (name "/+3.3V") (class "Default")
      (node (ref "C16") (pin "2") (pinfunction "2_2") (pintype "passive"))
      (node (ref "C2") (pin "2") (pinfunction "2_2") (pintype "passive"))
      (node (ref "C24") (pin "2") (pinfunction "2_2") (pintype "passive"))
      (node (ref "C3") (pin "2") (pinfunction "2_2") (pintype "passive"))
      (node (ref "C37") (pin "2") (pinfunction "2_2") (pintype "passive"))
      (node (ref "C39") (pin "1") (pinfunction "1_1") (pintype "passive"))
      (node (ref "C40") (pin "2") (pinfunction "2_2") (pintype "passive"))
      (node (ref "C41") (pin "2") (pinfunction "2_2") (pintype "passive"))
      (node (ref "C42") (pin "2") (pinfunction "2_2") (pintype "passive"))
      (node (ref "C43") (pin "2") (pinfunction "2_2") (pintype "passive"))
      (node (ref "C44") (pin "2") (pinfunction "2_2") (pintype "passive"))
      (node (ref "C45") (pin "2") (pinfunction "2_2") (pintype "passive"))
      (node (ref "C46") (pin "2") (pinfunction "2_2") (pintype "passive"))
      (node (ref "J2") (pin "1") (pinfunction "1_1") (pintype "bidirectional"))
      (node (ref "J3") (pin "1") (pinfunction "1_1") (pintype "bidirectional"))
      (node (ref "J4") (pin "1") (pinfunction "1_1") (pintype "bidirectional"))
      (node (ref "J5") (pin "9") (pinfunction "9_9") (pintype "bidirectional"))
      (node (ref "J6") (pin "1") (pinfunction "1_1") (pintype "bidirectional"))
      (node (ref "L1") (pin "1") (pinfunction "1_1") (pintype "passive"))
      (node (ref "L5") (pin "2") (pinfunction "2_2") (pintype "passive"))
      (node (ref "Q2") (pin "2") (pinfunction "E_2") (pintype "passive"))
      (node (ref "R10") (pin "2") (pinfunction "2_2") (pintype "passive"))
      (node (ref "R25") (pin "2") (pinfunction "2_2") (pintype "passive"))
      (node (ref "R26") (pin "2") (pinfunction "2_2") (pintype "passive"))
      (node (ref "R27") (pin "2") (pinfunction "2_2") (pintype "passive"))
      (node (ref "R28") (pin "2") (pinfunction "2_2") (pintype "passive"))
      (node (ref "R29") (pin "2") (pinfunction "2_2") (pintype "passive"))
      (node (ref "U3") (pin "4") (pinfunction "VCC_4") (pintype "power_in"))
      (node (ref "U5") (pin "1") (pinfunction "VOUT_1") (pintype "power_in"))
      (node (ref "U5") (pin "10") (pinfunction "FB_10") (pintype "input"))
      (node (ref "U6") (pin "9") (pinfunction "VDDIO_9") (pintype "power_in"))
      (node (ref "U7") (pin "100") (pinfunction "VDD_100") (pintype "power_in"))
      (node (ref "U7") (pin "11") (pinfunction "VDD_11") (pintype "power_in"))
      (node (ref "U7") (pin "19") (pinfunction "VDD_19") (pintype "power_in"))
      (node (ref "U7") (pin "21") (pinfunction "VREF+_21") (pintype "power_in"))
      (node (ref "U7") (pin "22") (pinfunction "VDDA_22") (pintype "power_in"))
      (node (ref "U7") (pin "28") (pinfunction "VDD_28") (pintype "power_in"))
      (node (ref "U7") (pin "50") (pinfunction "VDD_50") (pintype "power_in"))
      (node (ref "U7") (pin "75") (pinfunction "VDD_75") (pintype "power_in"))
    )
    (net (code "2") (name "/400V") (class "Default")
      (node (ref "B1") (pin "1") (pinfunction "1_1") (pintype "bidirectional"))
      (node (ref "C7") (pin "2") (pinfunction "2_2") (pintype "passive"))
      (node (ref "D8") (pin "3") (pinfunction "C_3") (pintype "passive"))
    )
    (net (code "3") (name "/ADC12_IN4") (class "Default")
      (node (ref "C38") (pin "2") (pinfunction "2_2") (pintype "passive"))
      (node (ref "R7") (pin "2") (pinfunction "2_2") (pintype "passive"))
      (node (ref "R9") (pin "2") (pinfunction "2_2") (pintype "passive"))
      (node (ref "U7") (pin "29") (pinfunction "PA4_29") (pintype "bidirectional"))
    )
    (net (code "4") (name "/BAT") (class "Default")
      (node (ref "J7") (pin "2") (pinfunction "2_2") (pintype "bidirectional"))
      (node (ref "Q3") (pin "2") (pinfunction "S_2") (pintype "passive"))
      (node (ref "R30") (pin "2") (pinfunction "2_2") (pintype "passive"))
      (node (ref "R31") (pin "2") (pinfunction "2_2") (pintype "passive"))
    )
    (net (code "5") (name "/BOOT0") (class "Default")
      (node (ref "J4") (pin "2") (pinfunction "2_2") (pintype "bidirectional"))
      (node (ref "R4") (pin "1") (pinfunction "1_1") (pintype "passive"))
      (node (ref "U7") (pin "94") (pinfunction "BOOT0_94") (pintype "input"))
    )
    (net (code "6") (name "/BTS") (class "Default")
      (node (ref "R17") (pin "1") (pinfunction "1_1") (pintype "passive"))
      (node (ref "R18") (pin "2") (pinfunction "2_2") (pintype "passive"))
      (node (ref "U2") (pin "11") (pinfunction "TS_11") (pintype "input"))
    )
    (net (code "7") (name "/B_DOWN") (class "Default")
      (node (ref "PB4") (pin "3") (pinfunction "3_3") (pintype "passive"))
      (node (ref "PB4") (pin "4") (pinfunction "4_4") (pintype "passive"))
      (node (ref "U7") (pin "61") (pinfunction "PD14_61") (pintype "bidirectional"))
    )
    (net (code "8") (name "/B_MODE") (class "Default")
      (node (ref "U7") (pin "4") (pinfunction "PE5_4") (pintype "bidirectional"))
    )
    (net (code "9") (name "/B_NEXT") (class "Default")
      (node (ref "D10") (pin "1") (pinfunction "C_1") (pintype "passive"))
      (node (ref "PB2") (pin "3") (pinfunction "3_3") (pintype "passive"))
      (node (ref "PB2") (pin "4") (pinfunction "4_4") (pintype "passive"))
      (node (ref "U7") (pin "2") (pinfunction "PE3_2") (pintype "bidirectional"))
    )
    (net (code "10") (name "/B_ONOFF") (class "Default")
      (node (ref "U7") (pin "1") (pinfunction "PE2_1") (pintype "bidirectional"))
    )
    (net (code "11") (name "/B_UP") (class "Default")
      (node (ref "PB3") (pin "3") (pinfunction "3_3") (pintype "passive"))
      (node (ref "PB3") (pin "4") (pinfunction "4_4") (pintype "passive"))
      (node (ref "U7") (pin "62") (pinfunction "PD15_62") (pintype "bidirectional"))
    )
    (net (code "12") (name "/B_VIEW") (class "Default")
      (node (ref "PB1") (pin "3") (pinfunction "3_3") (pintype "passive"))
      (node (ref "PB1") (pin "4") (pinfunction "4_4") (pintype "passive"))
      (node (ref "U7") (pin "3") (pinfunction "PE4_3") (pintype "bidirectional"))
    )
    (net (code "13") (name "/B_ZERO") (class "Default")
      (node (ref "U7") (pin "63") (pinfunction "PC6_63") (pintype "bidirectional"))
    )
    (net (code "14") (name "/CAN1_RX") (class "Default")
      (node (ref "TP9") (pin "1") (pinfunction "1_1") (pintype "passive"))
      (node (ref "U7") (pin "81") (pinfunction "PD0_81") (pintype "bidirectional"))
    )
    (net (code "15") (name "/CAN1_TX") (class "Default")
      (node (ref "TP8") (pin "1") (pinfunction "1_1") (pintype "passive"))
      (node (ref "U7") (pin "82") (pinfunction "PD1_82") (pintype "bidirectional"))
    )
    (net (code "16") (name "/CON_RX") (class "Default")
      (node (ref "J1") (pin "2") (pinfunction "2_2") (pintype "bidirectional"))
      (node (ref "R2") (pin "1") (pinfunction "1_1") (pintype "passive"))
    )
    (net (code "17") (name "/CON_TX") (class "Default")
      (node (ref "J1") (pin "3") (pinfunction "3_3") (pintype "bidirectional"))
      (node (ref "R3") (pin "1") (pinfunction "1_1") (pintype "passive"))
    )
    (net (code "18") (name "/DTOUT") (class "Default")
      (node (ref "Q2") (pin "3") (pinfunction "C_3") (pintype "passive"))
      (node (ref "R11") (pin "2") (pinfunction "2_2") (pintype "passive"))
      (node (ref "U7") (pin "30") (pinfunction "PA5_30") (pintype "bidirectional"))
    )
    (net (code "19") (name "/ETH_CRS_DV") (class "Default")
      (node (ref "R21") (pin "1") (pinfunction "1_1") (pintype "passive"))
      (node (ref "U7") (pin "32") (pinfunction "PA7_32") (pintype "bidirectional"))
    )
    (net (code "20") (name "/ETH_MDC") (class "Default")
      (node (ref "U6") (pin "13") (pinfunction "MDC_13") (pintype "input"))
      (node (ref "U7") (pin "16") (pinfunction "PC1_16") (pintype "bidirectional"))
    )
    (net (code "21") (name "/ETH_MDIO") (class "Default")
      (node (ref "R26") (pin "1") (pinfunction "1_1") (pintype "passive"))
      (node (ref "U6") (pin "12") (pinfunction "MDIO_12") (pintype "input"))
      (node (ref "U7") (pin "25") (pinfunction "PA2_25") (pintype "bidirectional"))
    )
    (net (code "22") (name "/ETH_REF_CLK") (class "Default")
      (node (ref "R22") (pin "1") (pinfunction "1_1") (pintype "passive"))
      (node (ref "TP4") (pin "1") (pinfunction "1_1") (pintype "passive"))
      (node (ref "U7") (pin "24") (pinfunction "PA1_24") (pintype "bidirectional"))
      (node (ref "U7") (pin "66") (pinfunction "PC9_66") (pintype "bidirectional"))
    )
    (net (code "23") (name "/ETH_RXD0") (class "Default")
      (node (ref "R19") (pin "1") (pinfunction "1_1") (pintype "passive"))
      (node (ref "U7") (pin "33") (pinfunction "PC4_33") (pintype "bidirectional"))
    )
    (net (code "24") (name "/ETH_RXD1") (class "Default")
      (node (ref "R20") (pin "1") (pinfunction "1_1") (pintype "passive"))
      (node (ref "U7") (pin "34") (pinfunction "PC5_34") (pintype "bidirectional"))
    )
    (net (code "25") (name "/ETH_TXD0") (class "Default")
      (node (ref "U6") (pin "17") (pinfunction "TXD0_17") (pintype "input"))
      (node (ref "U7") (pin "51") (pinfunction "PB12_51") (pintype "bidirectional"))
    )
    (net (code "26") (name "/ETH_TXD1") (class "Default")
      (node (ref "U6") (pin "18") (pinfunction "TXD1_18") (pintype "input"))
      (node (ref "U7") (pin "52") (pinfunction "PB13_52") (pintype "bidirectional"))
    )
    (net (code "27") (name "/ETH_TXEN") (class "Default")
      (node (ref "U6") (pin "16") (pinfunction "TXEN_16") (pintype "input"))
      (node (ref "U7") (pin "48") (pinfunction "PB11_48") (pintype "bidirectional"))
    )
    (net (code "28") (name "/GP_ETH_NINT") (class "Default")
      (node (ref "U6") (pin "14") (pinfunction "nINT/REFCLKO_14") (pintype "open_collector"))
      (node (ref "U7") (pin "18") (pinfunction "PC3_18") (pintype "bidirectional"))
    )
    (net (code "29") (name "/GP_ETH_NRST") (class "Default")
      (node (ref "R25") (pin "1") (pinfunction "1_1") (pintype "passive"))
      (node (ref "U6") (pin "15") (pinfunction "nRST_15") (pintype "input"))
      (node (ref "U7") (pin "17") (pinfunction "PC2_17") (pintype "bidirectional"))
    )
    (net (code "30") (name "/GP_GP0") (class "Default")
      (node (ref "J6") (pin "10") (pinfunction "10_10") (pintype "bidirectional"))
      (node (ref "U7") (pin "57") (pinfunction "PD10_57") (pintype "bidirectional"))
    )
    (net (code "31") (name "/GP_GP1") (class "Default")
      (node (ref "J6") (pin "9") (pinfunction "9_9") (pintype "bidirectional"))
      (node (ref "U7") (pin "58") (pinfunction "PD11_58") (pintype "bidirectional"))
    )
    (net (code "32") (name "/I2C1_SCL") (class "Default")
      (node (ref "R27") (pin "1") (pinfunction "1_1") (pintype "passive"))
      (node (ref "U2") (pin "5") (pinfunction "SCL_5") (pintype "input"))
      (node (ref "U3") (pin "1") (pinfunction "SCL_1") (pintype "input"))
      (node (ref "U7") (pin "95") (pinfunction "PB8_95") (pintype "bidirectional"))
    )
    (net (code "33") (name "/I2C1_SDA") (class "Default")
      (node (ref "R28") (pin "1") (pinfunction "1_1") (pintype "passive"))
      (node (ref "U2") (pin "6") (pinfunction "SDA_6") (pintype "bidirectional"))
      (node (ref "U3") (pin "3") (pinfunction "SDA_3") (pintype "open_collector"))
      (node (ref "U7") (pin "96") (pinfunction "PB9_96") (pintype "bidirectional"))
    )
    (net (code "34") (name "/LCD_CS") (class "Default")
      (node (ref "J6") (pin "6") (pinfunction "6_6") (pintype "bidirectional"))
      (node (ref "U7") (pin "87") (pinfunction "PD6_87") (pintype "bidirectional"))
    )
    (net (code "35") (name "/LCD_DC") (class "Default")
      (node (ref "J6") (pin "5") (pinfunction "5_5") (pintype "bidirectional"))
      (node (ref "U7") (pin "88") (pinfunction "PD7_88") (pintype "bidirectional"))
    )
    (net (code "36") (name "/LCD_LED_PWM") (class "Default")
      (node (ref "J6") (pin "8") (pinfunction "8_8") (pintype "bidirectional"))
      (node (ref "R8") (pin "1") (pinfunction "1_1") (pintype "passive"))
    )
    (net (code "37") (name "/LCD_RST") (class "Default")
      (node (ref "J6") (pin "7") (pinfunction "7_7") (pintype "bidirectional"))
      (node (ref "U7") (pin "86") (pinfunction "PD5_86") (pintype "bidirectional"))
    )
    (net (code "38") (name "/LED_ACT") (class "Default")
      (node (ref "R37") (pin "1") (pinfunction "1_1") (pintype "passive"))
      (node (ref "U6") (pin "3") (pinfunction "LED1/REGOFF_3") (pintype "output"))
    )
    (net (code "39") (name "/LED_GP") (class "Default")
      (node (ref "LD1") (pin "2") (pinfunction "A_2") (pintype "passive"))
      (node (ref "U7") (pin "44") (pinfunction "PE13_44") (pintype "bidirectional"))
    )
    (net (code "40") (name "/LED_SPEED") (class "Default")
      (node (ref "R38") (pin "1") (pinfunction "1_1") (pintype "passive"))
      (node (ref "U6") (pin "2") (pinfunction "LED2/nINTSEL_2") (pintype "output"))
    )
    (net (code "41") (name "/NRST") (class "Default")
      (node (ref "C49") (pin "2") (pinfunction "2_2") (pintype "passive"))
      (node (ref "U7") (pin "14") (pinfunction "NRST_14") (pintype "bidirectional"))
    )
    (net (code "42") (name "/OSC32_IN") (class "Default")
      (node (ref "C27") (pin "2") (pinfunction "2_2") (pintype "passive"))
      (node (ref "U7") (pin "8") (pinfunction "PC14/OSC32_IN_8") (pintype "bidirectional"))
      (node (ref "X1") (pin "2") (pinfunction "OSC2_2") (pintype "passive"))
    )
    (net (code "43") (name "/OSC32_OUT") (class "Default")
      (node (ref "C28") (pin "2") (pinfunction "2_2") (pintype "passive"))
      (node (ref "U7") (pin "9") (pinfunction "PC15/OSC32_OUT_9") (pintype "bidirectional"))
      (node (ref "X1") (pin "1") (pinfunction "OSC1_1") (pintype "passive"))
    )
    (net (code "44") (name "/OSC_IN") (class "Default")
      (node (ref "C30") (pin "2") (pinfunction "2_2") (pintype "passive"))
      (node (ref "U7") (pin "12") (pinfunction "PH0/OSC_IN_12") (pintype "bidirectional"))
      (node (ref "X2") (pin "3") (pinfunction "X_3") (pintype "passive"))
    )
    (net (code "45") (name "/OSC_OUT") (class "Default")
      (node (ref "C31") (pin "2") (pinfunction "2_2") (pintype "passive"))
      (node (ref "U7") (pin "13") (pinfunction "PH1/OSC_OUT_13") (pintype "bidirectional"))
      (node (ref "X2") (pin "1") (pinfunction "X_1") (pintype "passive"))
    )
    (net (code "46") (name "/PE1") (class "Default")
      (node (ref "D3") (pin "2") (pinfunction "A_2") (pintype "passive"))
      (node (ref "D4") (pin "1") (pinfunction "C_1") (pintype "passive"))
      (node (ref "T1") (pin "15") (pinfunction "RXCT_15") (pintype "bidirectional"))
    )
    (net (code "47") (name "/PE2") (class "Default")
      (node (ref "D6") (pin "2") (pinfunction "A_2") (pintype "passive"))
      (node (ref "D7") (pin "1") (pinfunction "C_1") (pintype "passive"))
      (node (ref "T1") (pin "10") (pinfunction "TXCT_10") (pintype "bidirectional"))
    )
    (net (code "48") (name "/POWER_ON") (class "Default")
      (node (ref "D10") (pin "2") (pinfunction "A_2") (pintype "passive"))
      (node (ref "Q3") (pin "1") (pinfunction "G_1") (pintype "passive"))
      (node (ref "R31") (pin "1") (pinfunction "1_1") (pintype "passive"))
    )
    (net (code "49") (name "/PULSE") (class "Default")
      (node (ref "B2") (pin "1") (pinfunction "1_1") (pintype "bidirectional"))
      (node (ref "R5") (pin "1") (pinfunction "1_1") (pintype "passive"))
    )
    (net (code "50") (name "/RCC_MCO1") (class "Default")
      (node (ref "TP3") (pin "1") (pinfunction "1_1") (pintype "passive"))
      (node (ref "U7") (pin "67") (pinfunction "PA8_67") (pintype "bidirectional"))
    )
    (net (code "51") (name "/RD_N") (class "Default")
      (node (ref "R33") (pin "1") (pinfunction "1_1") (pintype "passive"))
      (node (ref "T1") (pin "3") (pinfunction "RD-_3") (pintype "bidirectional"))
      (node (ref "U6") (pin "22") (pinfunction "RXN_22") (pintype "input"))
    )
    (net (code "52") (name "/RD_P") (class "Default")
      (node (ref "R34") (pin "1") (pinfunction "1_1") (pintype "passive"))
      (node (ref "T1") (pin "1") (pinfunction "RD+_1") (pintype "bidirectional"))
      (node (ref "U6") (pin "23") (pinfunction "RXP_23") (pintype "input"))
    )
    (net (code "53") (name "/REGN") (class "Default")
      (node (ref "C12") (pin "2") (pinfunction "2_2") (pintype "passive"))
      (node (ref "R17") (pin "2") (pinfunction "2_2") (pintype "passive"))
      (node (ref "U2") (pin "22") (pinfunction "REGN_22") (pintype "power_in"))
    )
    (net (code "54") (name "/RX_N") (class "Default")
      (node (ref "J8") (pin "3") (pinfunction "3_3") (pintype "bidirectional"))
      (node (ref "T1") (pin "14") (pinfunction "RX-_14") (pintype "bidirectional"))
    )
    (net (code "55") (name "/RX_P") (class "Default")
      (node (ref "J8") (pin "4") (pinfunction "4_4") (pintype "bidirectional"))
      (node (ref "T1") (pin "16") (pinfunction "RX+_16") (pintype "bidirectional"))
    )
    (net (code "56") (name "/SBAT") (class "Default")
      (node (ref "Q3") (pin "3") (pinfunction "D_3") (pintype "passive"))
      (node (ref "U2") (pin "13") (pinfunction "BAT_13") (pintype "power_in"))
      (node (ref "U2") (pin "14") (pinfunction "BAT_14") (pintype "power_in"))
    )
    (net (code "57") (name "/SPI3_CLK") (class "Default")
      (node (ref "J6") (pin "4") (pinfunction "4_4") (pintype "bidirectional"))
      (node (ref "U7") (pin "89") (pinfunction "PB3_89") (pintype "bidirectional"))
    )
    (net (code "58") (name "/SPI3_MISO") (class "Default")
      (node (ref "J6") (pin "3") (pinfunction "3_3") (pintype "bidirectional"))
      (node (ref "U7") (pin "90") (pinfunction "PB4_90") (pintype "bidirectional"))
    )
    (net (code "59") (name "/SPI3_MOSI") (class "Default")
      (node (ref "J6") (pin "2") (pinfunction "2_2") (pintype "bidirectional"))
      (node (ref "U7") (pin "91") (pinfunction "PB5_91") (pintype "bidirectional"))
    )
    (net (code "60") (name "/SWCLK") (class "Default")
      (node (ref "J3") (pin "2") (pinfunction "2_2") (pintype "bidirectional"))
      (node (ref "U7") (pin "76") (pinfunction "PA14_76") (pintype "bidirectional"))
    )
    (net (code "61") (name "/SWDIO") (class "Default")
      (node (ref "J3") (pin "4") (pinfunction "4_4") (pintype "bidirectional"))
      (node (ref "U7") (pin "72") (pinfunction "PA13_72") (pintype "bidirectional"))
    )
    (net (code "62") (name "/TD_N") (class "Default")
      (node (ref "R35") (pin "1") (pinfunction "1_1") (pintype "passive"))
      (node (ref "T1") (pin "8") (pinfunction "TD-_8") (pintype "bidirectional"))
      (node (ref "U6") (pin "20") (pinfunction "TXN_20") (pintype "output"))
    )
    (net (code "63") (name "/TD_P") (class "Default")
      (node (ref "R36") (pin "1") (pinfunction "1_1") (pintype "passive"))
      (node (ref "T1") (pin "6") (pinfunction "TD+_6") (pintype "bidirectional"))
      (node (ref "U6") (pin "21") (pinfunction "TXP_21") (pintype "output"))
    )
    (net (code "64") (name "/TIM3_CH1") (class "Default")
      (node (ref "Q1") (pin "1") (pinfunction "G_1") (pintype "passive"))
      (node (ref "R1") (pin "2") (pinfunction "2_2") (pintype "passive"))
      (node (ref "U7") (pin "31") (pinfunction "PA6_31") (pintype "bidirectional"))
    )
    (net (code "65") (name "/TIM8_CH2") (class "Default")
      (node (ref "R8") (pin "2") (pinfunction "2_2") (pintype "passive"))
      (node (ref "U7") (pin "64") (pinfunction "PC7_64") (pintype "bidirectional"))
    )
    (net (code "66") (name "/TIM12_CH1") (class "Default")
      (node (ref "LS1") (pin "1") (pinfunction "OSC1_1") (pintype "passive"))
      (node (ref "U7") (pin "53") (pinfunction "PB14_53") (pintype "bidirectional"))
    )
    (net (code "67") (name "/TIM12_CH2") (class "Default")
      (node (ref "R14") (pin "2") (pinfunction "2_2") (pintype "passive"))
      (node (ref "U7") (pin "54") (pinfunction "PB15_54") (pintype "bidirectional"))
    )
    (net (code "68") (name "/TX_N") (class "Default")
      (node (ref "J8") (pin "1") (pinfunction "1_1") (pintype "bidirectional"))
      (node (ref "T1") (pin "9") (pinfunction "TX-_9") (pintype "bidirectional"))
    )
    (net (code "69") (name "/TX_P") (class "Default")
      (node (ref "J8") (pin "2") (pinfunction "2_2") (pintype "bidirectional"))
      (node (ref "T1") (pin "11") (pinfunction "TX+_11") (pintype "bidirectional"))
    )
    (net (code "70") (name "/UART1_RX") (class "Default")
      (node (ref "R2") (pin "2") (pinfunction "2_2") (pintype "passive"))
      (node (ref "U4") (pin "6") (pinfunction "I/O4_6") (pintype "bidirectional"))
      (node (ref "U7") (pin "93") (pinfunction "PB7_93") (pintype "bidirectional"))
    )
    (net (code "71") (name "/UART1_TX") (class "Default")
      (node (ref "R3") (pin "2") (pinfunction "2_2") (pintype "passive"))
      (node (ref "U4") (pin "4") (pinfunction "I/O3_4") (pintype "bidirectional"))
      (node (ref "U7") (pin "92") (pinfunction "PB6_92") (pintype "bidirectional"))
    )
    (net (code "72") (name "/UART3_RX") (class "Default")
      (node (ref "J6") (pin "11") (pinfunction "11_11") (pintype "bidirectional"))
      (node (ref "U7") (pin "56") (pinfunction "PD9_56") (pintype "bidirectional"))
    )
    (net (code "73") (name "/UART3_TX") (class "Default")
      (node (ref "J6") (pin "12") (pinfunction "12_12") (pintype "bidirectional"))
      (node (ref "U7") (pin "55") (pinfunction "PD8_55") (pintype "bidirectional"))
    )
    (net (code "74") (name "/UART4_RX") (class "Default")
      (node (ref "J2") (pin "4") (pinfunction "4_4") (pintype "bidirectional"))
      (node (ref "U7") (pin "79") (pinfunction "PC11_79") (pintype "bidirectional"))
    )
    (net (code "75") (name "/UART4_TX") (class "Default")
      (node (ref "J2") (pin "2") (pinfunction "2_2") (pintype "bidirectional"))
      (node (ref "U7") (pin "78") (pinfunction "PC10_78") (pintype "bidirectional"))
    )
    (net (code "76") (name "/USB_OTG_FS_DM") (class "Default")
      (node (ref "TP6") (pin "1") (pinfunction "1_1") (pintype "passive"))
      (node (ref "U7") (pin "70") (pinfunction "PA11_70") (pintype "bidirectional"))
    )
    (net (code "77") (name "/USB_OTG_FS_DP") (class "Default")
      (node (ref "TP5") (pin "1") (pinfunction "1_1") (pintype "passive"))
      (node (ref "U7") (pin "71") (pinfunction "PA12_71") (pintype "bidirectional"))
    )
    (net (code "78") (name "/USB_OTG_FS_ID") (class "Default")
      (node (ref "TP7") (pin "1") (pinfunction "1_1") (pintype "passive"))
      (node (ref "U7") (pin "69") (pinfunction "PA10_69") (pintype "bidirectional"))
    )
    (net (code "79") (name "/USB_OTG_FS_VBUS") (class "Default")
      (node (ref "U7") (pin "68") (pinfunction "PA9_68") (pintype "bidirectional"))
    )
    (net (code "80") (name "/VBAT") (class "Default")
      (node (ref "C1") (pin "2") (pinfunction "2_2") (pintype "passive"))
      (node (ref "SK1") (pin "1") (pinfunction "1_1") (pintype "bidirectional"))
      (node (ref "U7") (pin "6") (pinfunction "VBAT_6") (pintype "power_in"))
    )
    (net (code "81") (name "/VCAP1") (class "Default")
      (node (ref "C47") (pin "2") (pinfunction "2_2") (pintype "passive"))
      (node (ref "U7") (pin "49") (pinfunction "VCAP_1_49") (pintype "power_in"))
    )
    (net (code "82") (name "/VCAP2") (class "Default")
      (node (ref "C48") (pin "2") (pinfunction "2_2") (pintype "passive"))
      (node (ref "U7") (pin "73") (pinfunction "VCAP_2_73") (pintype "power_in"))
    )
    (net (code "83") (name "/VCH") (class "Default")
      (node (ref "C10") (pin "2") (pinfunction "2_2") (pintype "passive"))
      (node (ref "C20") (pin "1") (pinfunction "1_1") (pintype "passive"))
      (node (ref "C21") (pin "1") (pinfunction "1_1") (pintype "passive"))
      (node (ref "C23") (pin "1") (pinfunction "1_1") (pintype "passive"))
      (node (ref "J1") (pin "4") (pinfunction "4_4") (pintype "bidirectional"))
      (node (ref "L2") (pin "2") (pinfunction "2_2") (pintype "passive"))
      (node (ref "R23") (pin "2") (pinfunction "2_2") (pintype "passive"))
      (node (ref "R29") (pin "1") (pinfunction "1_1") (pintype "passive"))
      (node (ref "U2") (pin "1") (pinfunction "VBUS_1") (pintype "power_in"))
    )
    (net (code "84") (name "/VDD_LAN") (class "Default")
      (node (ref "C29") (pin "1") (pinfunction "1_1") (pintype "passive"))
      (node (ref "C32") (pin "2") (pinfunction "2_2") (pintype "passive"))
      (node (ref "C33") (pin "2") (pinfunction "2_2") (pintype "passive"))
      (node (ref "C34") (pin "2") (pinfunction "2_2") (pintype "passive"))
      (node (ref "C35") (pin "1") (pinfunction "1_1") (pintype "passive"))
      (node (ref "C36") (pin "1") (pinfunction "1_1") (pintype "passive"))
      (node (ref "L5") (pin "1") (pinfunction "1_1") (pintype "passive"))
      (node (ref "LD2") (pin "2") (pinfunction "A_2") (pintype "passive"))
      (node (ref "R33") (pin "2") (pinfunction "2_2") (pintype "passive"))
      (node (ref "R34") (pin "2") (pinfunction "2_2") (pintype "passive"))
      (node (ref "R35") (pin "2") (pinfunction "2_2") (pintype "passive"))
      (node (ref "R36") (pin "2") (pinfunction "2_2") (pintype "passive"))
      (node (ref "T1") (pin "2") (pinfunction "RDCT_2") (pintype "bidirectional"))
      (node (ref "T1") (pin "7") (pinfunction "TDCT_7") (pintype "bidirectional"))
      (node (ref "U6") (pin "1") (pinfunction "VDD2A_1") (pintype "power_in"))
      (node (ref "U6") (pin "19") (pinfunction "VDD1A_19") (pintype "power_in"))
    )
    (net (code "85") (name "/VPOE") (class "Default")
      (node (ref "C13") (pin "1") (pinfunction "1_1") (pintype "passive"))
      (node (ref "C8") (pin "1") (pinfunction "1_1") (pintype "passive"))
      (node (ref "D3") (pin "1") (pinfunction "C_1") (pintype "passive"))
      (node (ref "D6") (pin "1") (pinfunction "C_1") (pintype "passive"))
      (node (ref "U1") (pin "2") (pinfunction "VIN_2") (pintype "power_in"))
    )
    (net (code "86") (name "/VSYS") (class "Default")
      (node (ref "C19") (pin "2") (pinfunction "2_2") (pintype "passive"))
      (node (ref "C22") (pin "2") (pinfunction "2_2") (pintype "passive"))
      (node (ref "L3") (pin "2") (pinfunction "2_2") (pintype "passive"))
      (node (ref "R30") (pin "1") (pinfunction "1_1") (pintype "passive"))
      (node (ref "U2") (pin "15") (pinfunction "SYS_15") (pintype "power_in"))
      (node (ref "U2") (pin "16") (pinfunction "SYS_16") (pintype "power_in"))
      (node (ref "U5") (pin "5") (pinfunction "VIN_5") (pintype "power_in"))
      (node (ref "U5") (pin "6") (pinfunction "EN_6") (pintype "input"))
      (node (ref "U5") (pin "7") (pinfunction "PS/SYNC_7") (pintype "input"))
      (node (ref "U5") (pin "8") (pinfunction "VINA_8") (pintype "power_in"))
    )
    (net (code "87") (name "0V") (class "Default")
      (node (ref "B3") (pin "1") (pinfunction "1_1") (pintype "bidirectional"))
      (node (ref "C1") (pin "1") (pinfunction "1_1") (pintype "passive"))
      (node (ref "C10") (pin "1") (pinfunction "1_1") (pintype "passive"))
      (node (ref "C11") (pin "1") (pinfunction "1_1") (pintype "passive"))
      (node (ref "C12") (pin "1") (pinfunction "1_1") (pintype "passive"))
      (node (ref "C13") (pin "2") (pinfunction "2_2") (pintype "passive"))
      (node (ref "C16") (pin "1") (pinfunction "1_1") (pintype "passive"))
      (node (ref "C17") (pin "1") (pinfunction "1_1") (pintype "passive"))
      (node (ref "C18") (pin "1") (pinfunction "1_1") (pintype "passive"))
      (node (ref "C19") (pin "1") (pinfunction "1_1") (pintype "passive"))
      (node (ref "C2") (pin "1") (pinfunction "1_1") (pintype "passive"))
      (node (ref "C20") (pin "2") (pinfunction "2_2") (pintype "passive"))
      (node (ref "C21") (pin "2") (pinfunction "2_2") (pintype "passive"))
      (node (ref "C22") (pin "1") (pinfunction "1_1") (pintype "passive"))
      (node (ref "C23") (pin "2") (pinfunction "2_2") (pintype "passive"))
      (node (ref "C24") (pin "1") (pinfunction "1_1") (pintype "passive"))
      (node (ref "C25") (pin "1") (pinfunction "1_1") (pintype "passive"))
      (node (ref "C26") (pin "1") (pinfunction "1_1") (pintype "passive"))
      (node (ref "C27") (pin "1") (pinfunction "1_1") (pintype "passive"))
      (node (ref "C28") (pin "1") (pinfunction "1_1") (pintype "passive"))
      (node (ref "C29") (pin "2") (pinfunction "2_2") (pintype "passive"))
      (node (ref "C3") (pin "1") (pinfunction "1_1") (pintype "passive"))
      (node (ref "C30") (pin "1") (pinfunction "1_1") (pintype "passive"))
      (node (ref "C31") (pin "1") (pinfunction "1_1") (pintype "passive"))
      (node (ref "C32") (pin "1") (pinfunction "1_1") (pintype "passive"))
      (node (ref "C33") (pin "1") (pinfunction "1_1") (pintype "passive"))
      (node (ref "C34") (pin "1") (pinfunction "1_1") (pintype "passive"))
      (node (ref "C35") (pin "2") (pinfunction "2_2") (pintype "passive"))
      (node (ref "C36") (pin "2") (pinfunction "2_2") (pintype "passive"))
      (node (ref "C37") (pin "1") (pinfunction "1_1") (pintype "passive"))
      (node (ref "C38") (pin "1") (pinfunction "1_1") (pintype "passive"))
      (node (ref "C39") (pin "2") (pinfunction "2_2") (pintype "passive"))
      (node (ref "C4") (pin "1") (pinfunction "1_1") (pintype "passive"))
      (node (ref "C40") (pin "1") (pinfunction "1_1") (pintype "passive"))
      (node (ref "C41") (pin "1") (pinfunction "1_1") (pintype "passive"))
      (node (ref "C42") (pin "1") (pinfunction "1_1") (pintype "passive"))
      (node (ref "C43") (pin "1") (pinfunction "1_1") (pintype "passive"))
      (node (ref "C44") (pin "1") (pinfunction "1_1") (pintype "passive"))
      (node (ref "C45") (pin "1") (pinfunction "1_1") (pintype "passive"))
      (node (ref "C46") (pin "1") (pinfunction "1_1") (pintype "passive"))
      (node (ref "C47") (pin "1") (pinfunction "1_1") (pintype "passive"))
      (node (ref "C48") (pin "1") (pinfunction "1_1") (pintype "passive"))
      (node (ref "C49") (pin "1") (pinfunction "1_1") (pintype "passive"))
      (node (ref "C5") (pin "1") (pinfunction "1_1") (pintype "passive"))
      (node (ref "C8") (pin "2") (pinfunction "2_2") (pintype "passive"))
      (node (ref "C9") (pin "1") (pinfunction "1_1") (pintype "passive"))
      (node (ref "D4") (pin "2") (pinfunction "A_2") (pintype "passive"))
      (node (ref "D7") (pin "2") (pinfunction "A_2") (pintype "passive"))
      (node (ref "D9") (pin "1") (pinfunction "A_1") (pintype "passive"))
      (node (ref "D9") (pin "2") (pinfunction "A_2") (pintype "passive"))
      (node (ref "J1") (pin "1") (pinfunction "1_1") (pintype "bidirectional"))
      (node (ref "J2") (pin "3") (pinfunction "3_3") (pintype "bidirectional"))
      (node (ref "J3") (pin "3") (pinfunction "3_3") (pintype "bidirectional"))
      (node (ref "J5") (pin "10") (pinfunction "10_10") (pintype "bidirectional"))
      (node (ref "J6") (pin "13") (pinfunction "13_13") (pintype "bidirectional"))
      (node (ref "J6") (pin "14") (pinfunction "14_14") (pintype "bidirectional"))
      (node (ref "J7") (pin "1") (pinfunction "1_1") (pintype "bidirectional"))
      (node (ref "L1") (pin "2") (pinfunction "2_2") (pintype "passive"))
      (node (ref "LD3") (pin "1") (pinfunction "C_1") (pintype "passive"))
      (node (ref "PB1") (pin "1") (pinfunction "1_1") (pintype "passive"))
      (node (ref "PB1") (pin "2") (pinfunction "2_2") (pintype "passive"))
      (node (ref "PB2") (pin "1") (pinfunction "1_1") (pintype "passive"))
      (node (ref "PB2") (pin "2") (pinfunction "2_2") (pintype "passive"))
      (node (ref "PB3") (pin "1") (pinfunction "1_1") (pintype "passive"))
      (node (ref "PB3") (pin "2") (pinfunction "2_2") (pintype "passive"))
      (node (ref "PB4") (pin "1") (pinfunction "1_1") (pintype "passive"))
      (node (ref "PB4") (pin "2") (pinfunction "2_2") (pintype "passive"))
      (node (ref "Q1") (pin "2") (pinfunction "S_2") (pintype "passive"))
      (node (ref "R1") (pin "1") (pinfunction "1_1") (pintype "passive"))
      (node (ref "R11") (pin "1") (pinfunction "1_1") (pintype "passive"))
      (node (ref "R12") (pin "1") (pinfunction "1_1") (pintype "passive"))
      (node (ref "R13") (pin "1") (pinfunction "1_1") (pintype "passive"))
      (node (ref "R15") (pin "2") (pinfunction "2_2") (pintype "passive"))
      (node (ref "R18") (pin "1") (pinfunction "1_1") (pintype "passive"))
      (node (ref "R24") (pin "1") (pinfunction "1_1") (pintype "passive"))
      (node (ref "R32") (pin "2") (pinfunction "2_2") (pintype "passive"))
      (node (ref "R4") (pin "2") (pinfunction "2_2") (pintype "passive"))
      (node (ref "R9") (pin "1") (pinfunction "1_1") (pintype "passive"))
      (node (ref "SK1") (pin "2") (pinfunction "2_2") (pintype "bidirectional"))
      (node (ref "TP2") (pin "1") (pinfunction "1_1") (pintype "passive"))
      (node (ref "U1") (pin "11") (pinfunction "EP_11") (pintype "power_in"))
      (node (ref "U1") (pin "6") (pinfunction "PWRGD_6") (pintype "power_in"))
      (node (ref "U1") (pin "9") (pinfunction "GND_9") (pintype "power_in"))
      (node (ref "U2") (pin "17") (pinfunction "PGND_17") (pintype "power_in"))
      (node (ref "U2") (pin "18") (pinfunction "PGND_18") (pintype "power_in"))
      (node (ref "U2") (pin "25") (pinfunction "PGND_25") (pintype "power_in"))
      (node (ref "U3") (pin "2") (pinfunction "GND_2") (pintype "power_in"))
      (node (ref "U3") (pin "5") (pinfunction "WP_5") (pintype "input"))
      (node (ref "U4") (pin "2") (pinfunction "VN_2") (pintype "power_in"))
      (node (ref "U5") (pin "11") (pinfunction "TP_11") (pintype "power_in"))
      (node (ref "U5") (pin "3") (pinfunction "PGND_3") (pintype "power_in"))
      (node (ref "U5") (pin "9") (pinfunction "GND_9") (pintype "power_in"))
      (node (ref "U6") (pin "25") (pinfunction "VSS_PAD_25") (pintype "power_in"))
      (node (ref "U7") (pin "10") (pinfunction "VSS_10") (pintype "power_in"))
      (node (ref "U7") (pin "20") (pinfunction "VSSA_20") (pintype "power_in"))
      (node (ref "U7") (pin "27") (pinfunction "VSS_27") (pintype "power_in"))
      (node (ref "U7") (pin "37") (pinfunction "PB2/BOOT1_37") (pintype "bidirectional"))
      (node (ref "U7") (pin "74") (pinfunction "VSS_74") (pintype "power_in"))
      (node (ref "U7") (pin "99") (pinfunction "VSS_99") (pintype "power_in"))
      (node (ref "X2") (pin "2") (pinfunction "GND_2") (pintype "power_in"))
      (node (ref "X2") (pin "4") (pinfunction "GND_4") (pintype "power_in"))
    )
    (net (code "88") (name "Net-(C15-Pad2)") (class "Default")
      (node (ref "C15") (pin "2") (pinfunction "2_2") (pintype "passive"))
      (node (ref "L3") (pin "1") (pinfunction "1_1") (pintype "passive"))
      (node (ref "U2") (pin "19") (pinfunction "LX_19") (pintype "output"))
      (node (ref "U2") (pin "20") (pinfunction "LX_20") (pintype "output"))
    )
    (net (code "89") (name "Net-(C17-Pad2)") (class "Default")
      (node (ref "C17") (pin "2") (pinfunction "2_2") (pintype "passive"))
      (node (ref "R16") (pin "1") (pinfunction "1_1") (pintype "passive"))
    )
    (net (code "90") (name "Net-(D1-A)") (class "Default")
      (node (ref "D1") (pin "1") (pinfunction "A_1") (pintype "passive"))
      (node (ref "L1") (pin "4") (pinfunction "4_4") (pintype "passive"))
      (node (ref "Q1") (pin "3") (pinfunction "D_3") (pintype "passive"))
    )
    (net (code "91") (name "Net-(D1-C)") (class "Default")
      (node (ref "C4") (pin "2") (pinfunction "2_2") (pintype "passive"))
      (node (ref "D1") (pin "3") (pinfunction "C_3") (pintype "passive"))
      (node (ref "R7") (pin "1") (pinfunction "1_1") (pintype "passive"))
    )
    (net (code "92") (name "Net-(D2-A)") (class "Default")
      (node (ref "C6") (pin "1") (pinfunction "1_1") (pintype "passive"))
      (node (ref "D2") (pin "1") (pinfunction "A_1") (pintype "passive"))
      (node (ref "L1") (pin "3") (pinfunction "3_3") (pintype "passive"))
    )
    (net (code "93") (name "Net-(D2-C)") (class "Default")
      (node (ref "C5") (pin "2") (pinfunction "2_2") (pintype "passive"))
      (node (ref "C7") (pin "1") (pinfunction "1_1") (pintype "passive"))
      (node (ref "D2") (pin "3") (pinfunction "C_3") (pintype "passive"))
      (node (ref "D5") (pin "1") (pinfunction "A_1") (pintype "passive"))
    )
    (net (code "94") (name "Net-(D5-C)") (class "Default")
      (node (ref "C6") (pin "2") (pinfunction "2_2") (pintype "passive"))
      (node (ref "D5") (pin "3") (pinfunction "C_3") (pintype "passive"))
      (node (ref "D8") (pin "1") (pinfunction "A_1") (pintype "passive"))
    )
    (net (code "95") (name "Net-(D9-C)") (class "Default")
      (node (ref "C14") (pin "2") (pinfunction "2_2") (pintype "passive"))
      (node (ref "D9") (pin "3") (pinfunction "C_3") (pintype "passive"))
      (node (ref "L2") (pin "1") (pinfunction "1_1") (pintype "passive"))
      (node (ref "U1") (pin "10") (pinfunction "PH_10") (pintype "output"))
    )
    (net (code "96") (name "Net-(LD1-C)") (class "Default")
      (node (ref "LD1") (pin "1") (pinfunction "C_1") (pintype "passive"))
      (node (ref "R15") (pin "1") (pinfunction "1_1") (pintype "passive"))
    )
    (net (code "97") (name "Net-(LD2-C)") (class "Default")
      (node (ref "LD2") (pin "1") (pinfunction "C_1") (pintype "passive"))
      (node (ref "R38") (pin "2") (pinfunction "2_2") (pintype "passive"))
    )
    (net (code "98") (name "Net-(LD3-A)") (class "Default")
      (node (ref "LD3") (pin "2") (pinfunction "A_2") (pintype "passive"))
      (node (ref "R37") (pin "2") (pinfunction "2_2") (pintype "passive"))
    )
    (net (code "99") (name "Net-(LS1-OSC2)") (class "Default")
      (node (ref "LS1") (pin "2") (pinfunction "OSC2_2") (pintype "passive"))
      (node (ref "R14") (pin "1") (pinfunction "1_1") (pintype "passive"))
    )
    (net (code "100") (name "Net-(Q2-B)") (class "Default")
      (node (ref "Q2") (pin "1") (pinfunction "B_1") (pintype "passive"))
      (node (ref "R10") (pin "1") (pinfunction "1_1") (pintype "passive"))
      (node (ref "R6") (pin "2") (pinfunction "2_2") (pintype "passive"))
    )
    (net (code "101") (name "Net-(R5-Pad2)") (class "Default")
      (node (ref "R5") (pin "2") (pinfunction "2_2") (pintype "passive"))
      (node (ref "R6") (pin "1") (pinfunction "1_1") (pintype "passive"))
    )
    (net (code "102") (name "Net-(U1-BOOT)") (class "Default")
      (node (ref "C14") (pin "1") (pinfunction "1_1") (pintype "passive"))
      (node (ref "U1") (pin "1") (pinfunction "BOOT_1") (pintype "input"))
    )
    (net (code "103") (name "Net-(U1-COMP)") (class "Default")
      (node (ref "C18") (pin "2") (pinfunction "2_2") (pintype "passive"))
      (node (ref "R16") (pin "2") (pinfunction "2_2") (pintype "passive"))
      (node (ref "U1") (pin "8") (pinfunction "COMP_8") (pintype "input"))
    )
    (net (code "104") (name "Net-(U1-RT{slash}CLK)") (class "Default")
      (node (ref "R13") (pin "2") (pinfunction "2_2") (pintype "passive"))
      (node (ref "U1") (pin "5") (pinfunction "RT/CLK_5") (pintype "input"))
    )
    (net (code "105") (name "Net-(U1-SS{slash}TR)") (class "Default")
      (node (ref "C9") (pin "2") (pinfunction "2_2") (pintype "passive"))
      (node (ref "U1") (pin "4") (pinfunction "SS/TR_4") (pintype "input"))
    )
    (net (code "106") (name "Net-(U1-VSENSE)") (class "Default")
      (node (ref "R23") (pin "1") (pinfunction "1_1") (pintype "passive"))
      (node (ref "R24") (pin "2") (pinfunction "2_2") (pintype "passive"))
      (node (ref "U1") (pin "7") (pinfunction "VSENSE_7") (pintype "input"))
    )
    (net (code "107") (name "Net-(U2-BTST)") (class "Default")
      (node (ref "C15") (pin "1") (pinfunction "1_1") (pintype "passive"))
      (node (ref "U2") (pin "21") (pinfunction "BTST_21") (pintype "input"))
    )
    (net (code "108") (name "Net-(U2-ILIM)") (class "Default")
      (node (ref "R12") (pin "2") (pinfunction "2_2") (pintype "passive"))
      (node (ref "U2") (pin "10") (pinfunction "ILIM_10") (pintype "input"))
    )
    (net (code "109") (name "Net-(U2-QON)") (class "Default")
      (node (ref "TP1") (pin "1") (pinfunction "1_1") (pintype "passive"))
      (node (ref "U2") (pin "12") (pinfunction "QON_12") (pintype "input"))
    )
    (net (code "110") (name "Net-(U2-VMID)") (class "Default")
      (node (ref "C11") (pin "2") (pinfunction "2_2") (pintype "passive"))
      (node (ref "U2") (pin "23") (pinfunction "VMID_23") (pintype "output"))
    )
    (net (code "111") (name "Net-(U5-L1)") (class "Default")
      (node (ref "L4") (pin "1") (pinfunction "1_1") (pintype "passive"))
      (node (ref "U5") (pin "4") (pinfunction "L1_4") (pintype "output"))
    )
    (net (code "112") (name "Net-(U5-L2)") (class "Default")
      (node (ref "L4") (pin "2") (pinfunction "2_2") (pintype "passive"))
      (node (ref "U5") (pin "2") (pinfunction "L2_2") (pintype "output"))
    )
    (net (code "113") (name "Net-(U6-CRS_DV{slash}MODE2)") (class "Default")
      (node (ref "R21") (pin "2") (pinfunction "2_2") (pintype "passive"))
      (node (ref "U6") (pin "11") (pinfunction "CRS_DV/MODE2_11") (pintype "output"))
    )
    (net (code "114") (name "Net-(U6-RBIAS)") (class "Default")
      (node (ref "R32") (pin "1") (pinfunction "1_1") (pintype "passive"))
      (node (ref "U6") (pin "24") (pinfunction "RBIAS_24") (pintype "input"))
    )
    (net (code "115") (name "Net-(U6-RXD0{slash}MODE0)") (class "Default")
      (node (ref "R19") (pin "2") (pinfunction "2_2") (pintype "passive"))
      (node (ref "U6") (pin "8") (pinfunction "RXD0/MODE0_8") (pintype "output"))
    )
    (net (code "116") (name "Net-(U6-RXD1{slash}MODE1)") (class "Default")
      (node (ref "R20") (pin "2") (pinfunction "2_2") (pintype "passive"))
      (node (ref "U6") (pin "7") (pinfunction "RXD1/MODE1_7") (pintype "output"))
    )
    (net (code "117") (name "Net-(U6-VDDCR)") (class "Default")
      (node (ref "C25") (pin "2") (pinfunction "2_2") (pintype "passive"))
      (node (ref "C26") (pin "2") (pinfunction "2_2") (pintype "passive"))
      (node (ref "U6") (pin "6") (pinfunction "VDDCR_6") (pintype "power_in"))
    )
    (net (code "118") (name "Net-(U6-XTAL1{slash}CLKIN)") (class "Default")
      (node (ref "R22") (pin "2") (pinfunction "2_2") (pintype "passive"))
      (node (ref "U6") (pin "5") (pinfunction "XTAL1/CLKIN_5") (pintype "input"))
    )
    (net (code "119") (name "unconnected-(J5-Pad1)") (class "Default")
      (node (ref "J5") (pin "1") (pinfunction "1_1") (pintype "bidirectional"))
    )
    (net (code "120") (name "unconnected-(J5-Pad2)") (class "Default")
      (node (ref "J5") (pin "2") (pinfunction "2_2") (pintype "bidirectional"))
    )
    (net (code "121") (name "unconnected-(J5-Pad3)") (class "Default")
      (node (ref "J5") (pin "3") (pinfunction "3_3") (pintype "bidirectional"))
    )
    (net (code "122") (name "unconnected-(J5-Pad4)") (class "Default")
      (node (ref "J5") (pin "4") (pinfunction "4_4") (pintype "bidirectional"))
    )
    (net (code "123") (name "unconnected-(J5-Pad5)") (class "Default")
      (node (ref "J5") (pin "5") (pinfunction "5_5") (pintype "bidirectional"))
    )
    (net (code "124") (name "unconnected-(J5-Pad6)") (class "Default")
      (node (ref "J5") (pin "6") (pinfunction "6_6") (pintype "bidirectional"))
    )
    (net (code "125") (name "unconnected-(J5-Pad7)") (class "Default")
      (node (ref "J5") (pin "7") (pinfunction "7_7") (pintype "bidirectional"))
    )
    (net (code "126") (name "unconnected-(J5-Pad8)") (class "Default")
      (node (ref "J5") (pin "8") (pinfunction "8_8") (pintype "bidirectional"))
    )
    (net (code "127") (name "unconnected-(J5-Pad11)") (class "Default")
      (node (ref "J5") (pin "11") (pinfunction "11_11") (pintype "bidirectional"))
    )
    (net (code "128") (name "unconnected-(J5-Pad12)") (class "Default")
      (node (ref "J5") (pin "12") (pinfunction "12_12") (pintype "bidirectional"))
    )
    (net (code "129") (name "unconnected-(J5-Pad13)") (class "Default")
      (node (ref "J5") (pin "13") (pinfunction "13_13") (pintype "bidirectional"))
    )
    (net (code "130") (name "unconnected-(J5-Pad14)") (class "Default")
      (node (ref "J5") (pin "14") (pinfunction "14_14") (pintype "bidirectional"))
    )
    (net (code "131") (name "unconnected-(T1-NC-Pad4)") (class "Default")
      (node (ref "T1") (pin "4") (pinfunction "NC_4") (pintype "passive"))
    )
    (net (code "132") (name "unconnected-(T1-NC-Pad5)") (class "Default")
      (node (ref "T1") (pin "5") (pinfunction "NC_5") (pintype "passive"))
    )
    (net (code "133") (name "unconnected-(T1-NC-Pad12)") (class "Default")
      (node (ref "T1") (pin "12") (pinfunction "NC_12") (pintype "passive"))
    )
    (net (code "134") (name "unconnected-(T1-NC-Pad13)") (class "Default")
      (node (ref "T1") (pin "13") (pinfunction "NC_13") (pintype "passive"))
    )
    (net (code "135") (name "unconnected-(U1-EN-Pad3)") (class "Default")
      (node (ref "U1") (pin "3") (pinfunction "EN_3") (pintype "input"))
    )
    (net (code "136") (name "unconnected-(U2-CEB-Pad9)") (class "Default")
      (node (ref "U2") (pin "9") (pinfunction "CEB_9") (pintype "input"))
    )
    (net (code "137") (name "unconnected-(U2-INT-Pad7)") (class "Default")
      (node (ref "U2") (pin "7") (pinfunction "INT_7") (pintype "open_collector"))
    )
    (net (code "138") (name "unconnected-(U2-NC-Pad24)") (class "Default")
      (node (ref "U2") (pin "24") (pinfunction "NC_24") (pintype "passive"))
    )
    (net (code "139") (name "unconnected-(U2-OTG-Pad8)") (class "Default")
      (node (ref "U2") (pin "8") (pinfunction "OTG_8") (pintype "input"))
    )
    (net (code "140") (name "unconnected-(U2-PSEL-Pad2)") (class "Default")
      (node (ref "U2") (pin "2") (pinfunction "PSEL_2") (pintype "input"))
    )
    (net (code "141") (name "unconnected-(U2-STAT-Pad4)") (class "Default")
      (node (ref "U2") (pin "4") (pinfunction "STAT_4") (pintype "open_collector"))
    )
    (net (code "142") (name "unconnected-(U2-~{P}G-Pad3)") (class "Default")
      (node (ref "U2") (pin "3") (pinfunction "~{P}G_3") (pintype "open_collector"))
    )
    (net (code "143") (name "unconnected-(U4-I{slash}O1-Pad1)") (class "Default")
      (node (ref "U4") (pin "1") (pinfunction "I/O1_1") (pintype "bidirectional"))
    )
    (net (code "144") (name "unconnected-(U4-I{slash}O2-Pad3)") (class "Default")
      (node (ref "U4") (pin "3") (pinfunction "I/O2_3") (pintype "bidirectional"))
    )
    (net (code "145") (name "unconnected-(U4-VP-Pad5)") (class "Default")
      (node (ref "U4") (pin "5") (pinfunction "VP_5") (pintype "power_in"))
    )
    (net (code "146") (name "unconnected-(U6-RXER{slash}PHYAD0-Pad10)") (class "Default")
      (node (ref "U6") (pin "10") (pinfunction "RXER/PHYAD0_10") (pintype "output"))
    )
    (net (code "147") (name "unconnected-(U6-XTAL2-Pad4)") (class "Default")
      (node (ref "U6") (pin "4") (pinfunction "XTAL2_4") (pintype "output"))
    )
    (net (code "148") (name "unconnected-(U7-PA0{slash}WKUP-Pad23)") (class "Default")
      (node (ref "U7") (pin "23") (pinfunction "PA0/WKUP_23") (pintype "bidirectional"))
    )
    (net (code "149") (name "unconnected-(U7-PA3-Pad26)") (class "Default")
      (node (ref "U7") (pin "26") (pinfunction "PA3_26") (pintype "bidirectional"))
    )
    (net (code "150") (name "unconnected-(U7-PA15-Pad77)") (class "Default")
      (node (ref "U7") (pin "77") (pinfunction "PA15_77") (pintype "bidirectional"))
    )
    (net (code "151") (name "unconnected-(U7-PB0-Pad35)") (class "Default")
      (node (ref "U7") (pin "35") (pinfunction "PB0_35") (pintype "bidirectional"))
    )
    (net (code "152") (name "unconnected-(U7-PB1-Pad36)") (class "Default")
      (node (ref "U7") (pin "36") (pinfunction "PB1_36") (pintype "bidirectional"))
    )
    (net (code "153") (name "unconnected-(U7-PB10-Pad47)") (class "Default")
      (node (ref "U7") (pin "47") (pinfunction "PB10_47") (pintype "bidirectional"))
    )
    (net (code "154") (name "unconnected-(U7-PC0-Pad15)") (class "Default")
      (node (ref "U7") (pin "15") (pinfunction "PC0_15") (pintype "bidirectional"))
    )
    (net (code "155") (name "unconnected-(U7-PC8-Pad65)") (class "Default")
      (node (ref "U7") (pin "65") (pinfunction "PC8_65") (pintype "bidirectional"))
    )
    (net (code "156") (name "unconnected-(U7-PC12-Pad80)") (class "Default")
      (node (ref "U7") (pin "80") (pinfunction "PC12_80") (pintype "bidirectional"))
    )
    (net (code "157") (name "unconnected-(U7-PC13-Pad7)") (class "Default")
      (node (ref "U7") (pin "7") (pinfunction "PC13_7") (pintype "bidirectional"))
    )
    (net (code "158") (name "unconnected-(U7-PD2-Pad83)") (class "Default")
      (node (ref "U7") (pin "83") (pinfunction "PD2_83") (pintype "bidirectional"))
    )
    (net (code "159") (name "unconnected-(U7-PD3-Pad84)") (class "Default")
      (node (ref "U7") (pin "84") (pinfunction "PD3_84") (pintype "bidirectional"))
    )
    (net (code "160") (name "unconnected-(U7-PD4-Pad85)") (class "Default")
      (node (ref "U7") (pin "85") (pinfunction "PD4_85") (pintype "bidirectional"))
    )
    (net (code "161") (name "unconnected-(U7-PD12-Pad59)") (class "Default")
      (node (ref "U7") (pin "59") (pinfunction "PD12_59") (pintype "bidirectional"))
    )
    (net (code "162") (name "unconnected-(U7-PD13-Pad60)") (class "Default")
      (node (ref "U7") (pin "60") (pinfunction "PD13_60") (pintype "bidirectional"))
    )
    (net (code "163") (name "unconnected-(U7-PE0-Pad97)") (class "Default")
      (node (ref "U7") (pin "97") (pinfunction "PE0_97") (pintype "bidirectional"))
    )
    (net (code "164") (name "unconnected-(U7-PE1-Pad98)") (class "Default")
      (node (ref "U7") (pin "98") (pinfunction "PE1_98") (pintype "bidirectional"))
    )
    (net (code "165") (name "unconnected-(U7-PE6-Pad5)") (class "Default")
      (node (ref "U7") (pin "5") (pinfunction "PE6_5") (pintype "bidirectional"))
    )
    (net (code "166") (name "unconnected-(U7-PE7-Pad38)") (class "Default")
      (node (ref "U7") (pin "38") (pinfunction "PE7_38") (pintype "bidirectional"))
    )
    (net (code "167") (name "unconnected-(U7-PE8-Pad39)") (class "Default")
      (node (ref "U7") (pin "39") (pinfunction "PE8_39") (pintype "bidirectional"))
    )
    (net (code "168") (name "unconnected-(U7-PE9-Pad40)") (class "Default")
      (node (ref "U7") (pin "40") (pinfunction "PE9_40") (pintype "bidirectional"))
    )
    (net (code "169") (name "unconnected-(U7-PE10-Pad41)") (class "Default")
      (node (ref "U7") (pin "41") (pinfunction "PE10_41") (pintype "bidirectional"))
    )
    (net (code "170") (name "unconnected-(U7-PE11-Pad42)") (class "Default")
      (node (ref "U7") (pin "42") (pinfunction "PE11_42") (pintype "bidirectional"))
    )
    (net (code "171") (name "unconnected-(U7-PE12-Pad43)") (class "Default")
      (node (ref "U7") (pin "43") (pinfunction "PE12_43") (pintype "bidirectional"))
    )
    (net (code "172") (name "unconnected-(U7-PE14-Pad45)") (class "Default")
      (node (ref "U7") (pin "45") (pinfunction "PE14_45") (pintype "bidirectional"))
    )
    (net (code "173") (name "unconnected-(U7-PE15-Pad46)") (class "Default")
      (node (ref "U7") (pin "46") (pinfunction "PE15_46") (pintype "bidirectional"))
    )
  )
)
